# Zvuk9_R2.net
KiCad netlist of a schematic drawn in EAGLE
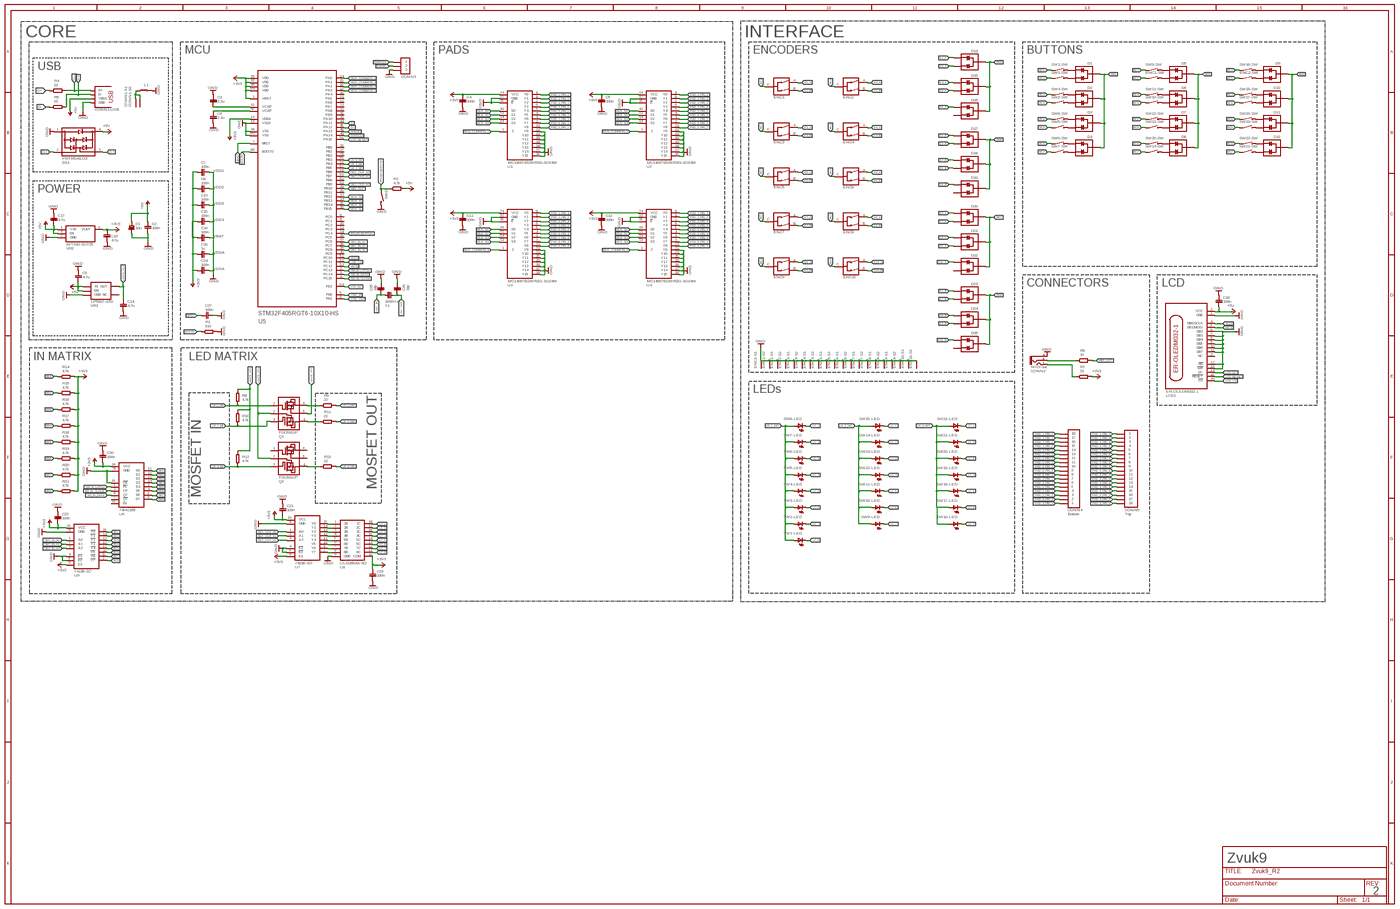
[diagram p0: schematic, sheet 1, overview]
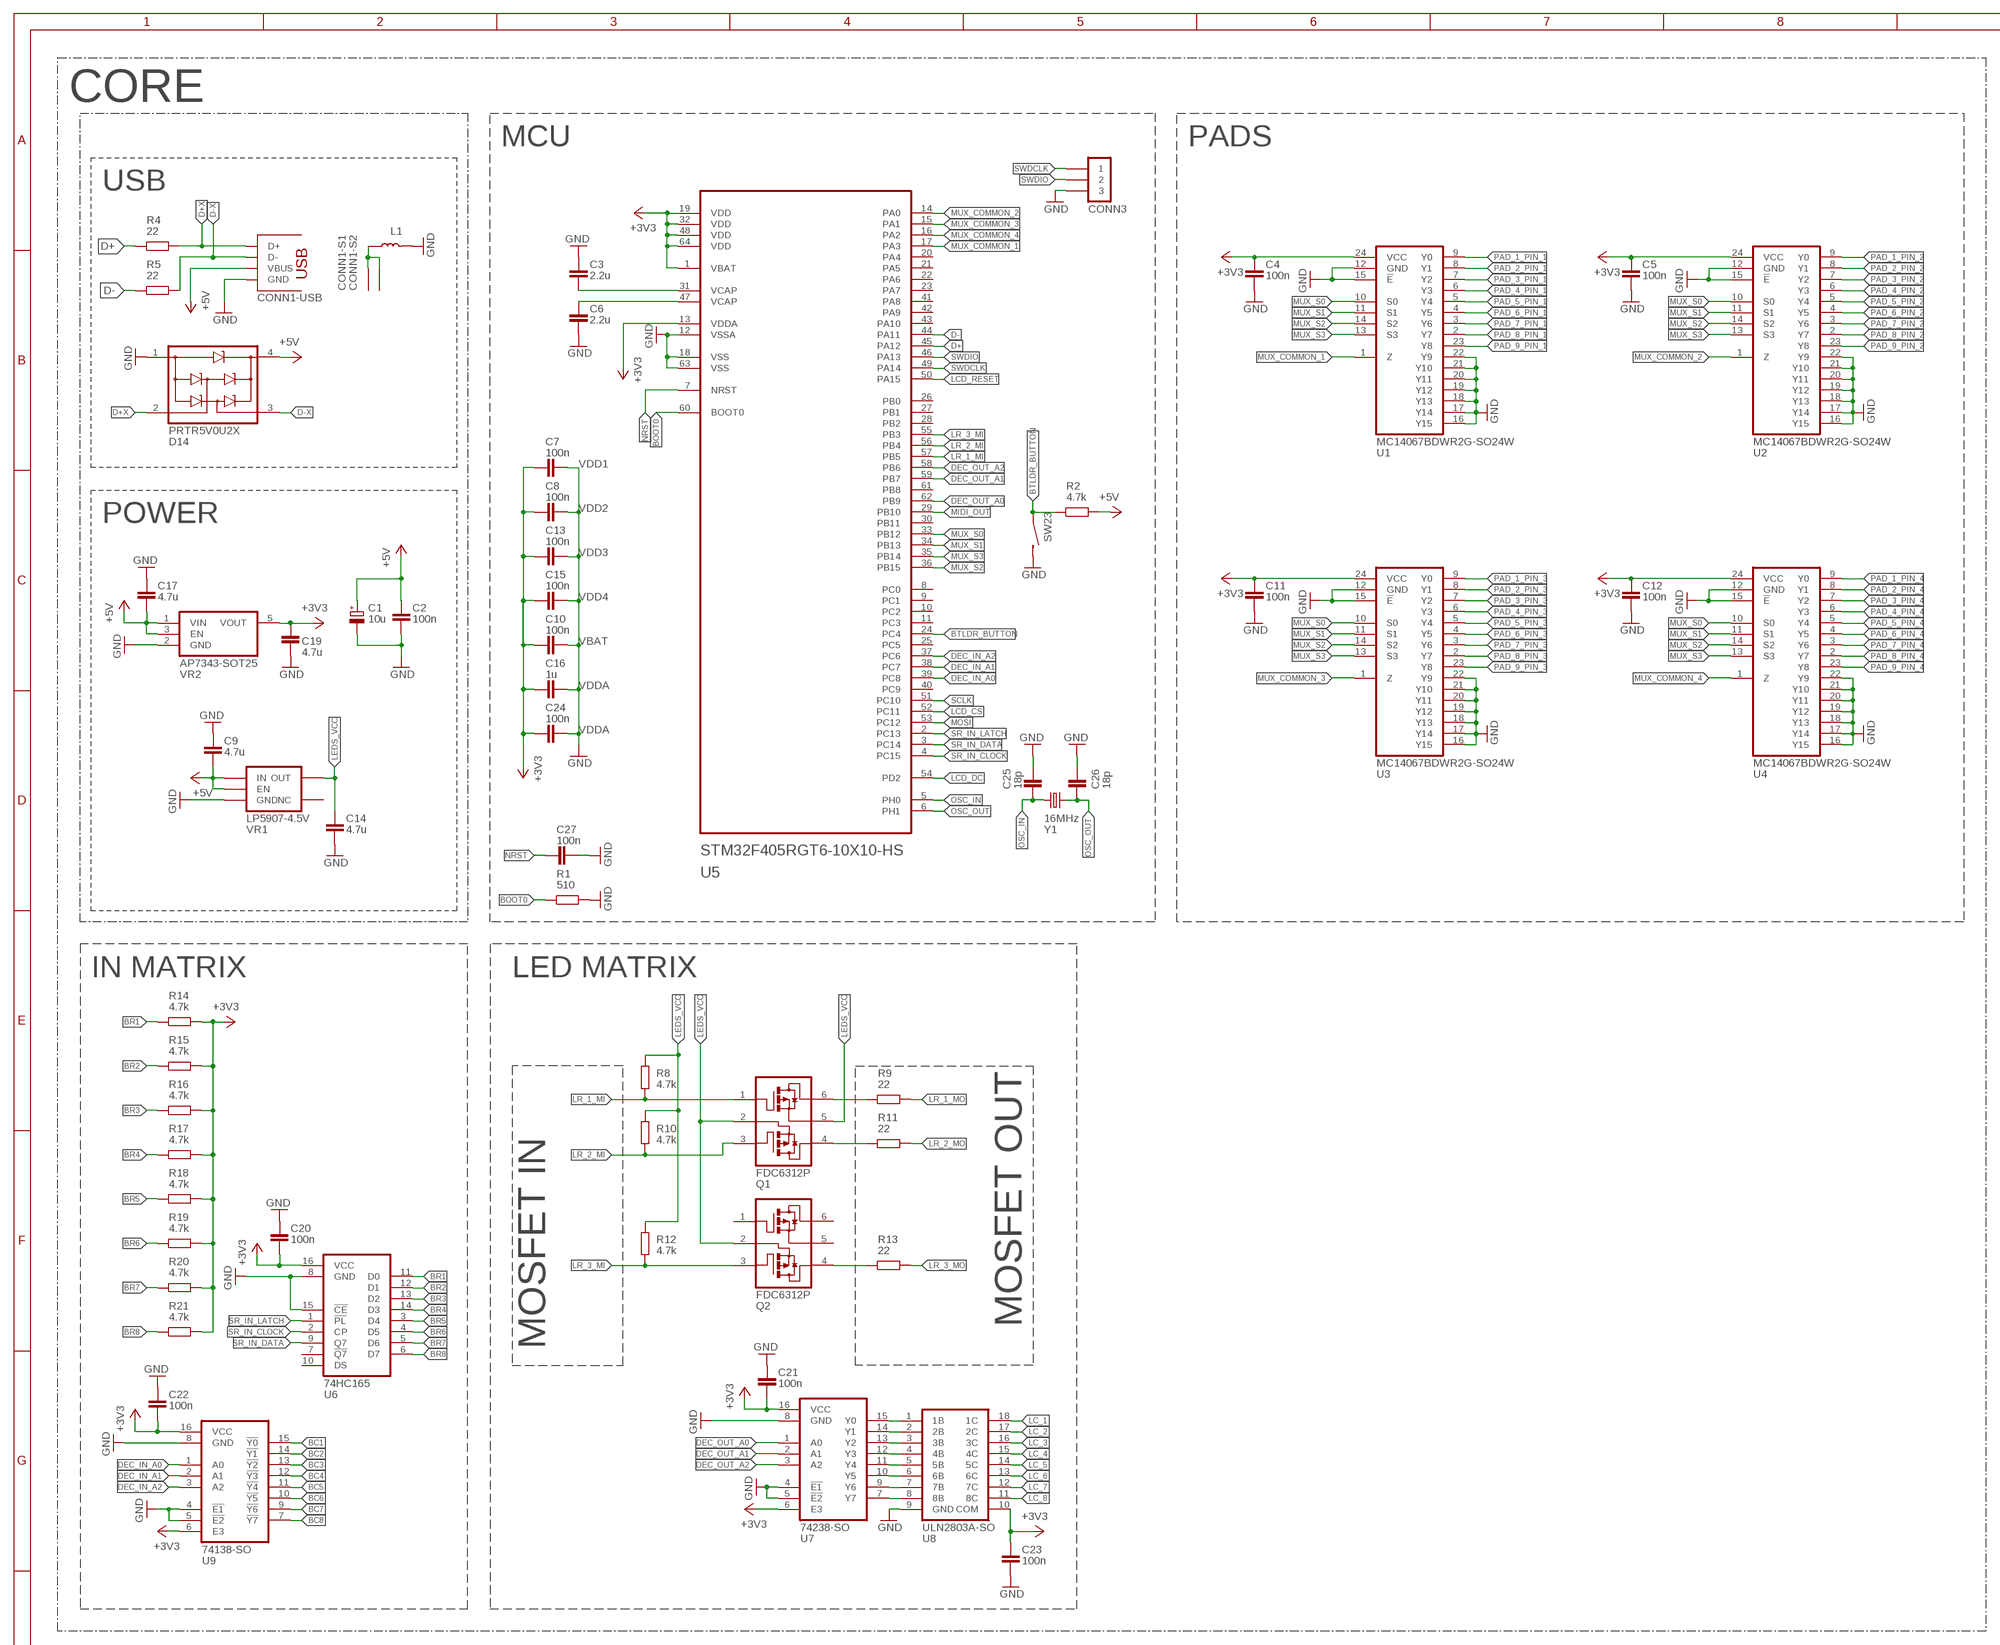
[diagram p1: schematic, sheet 1, part 1 of 4]
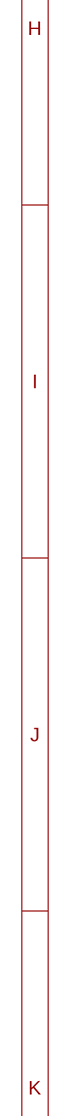
[diagram p2: schematic, sheet 1, part 2 of 4]
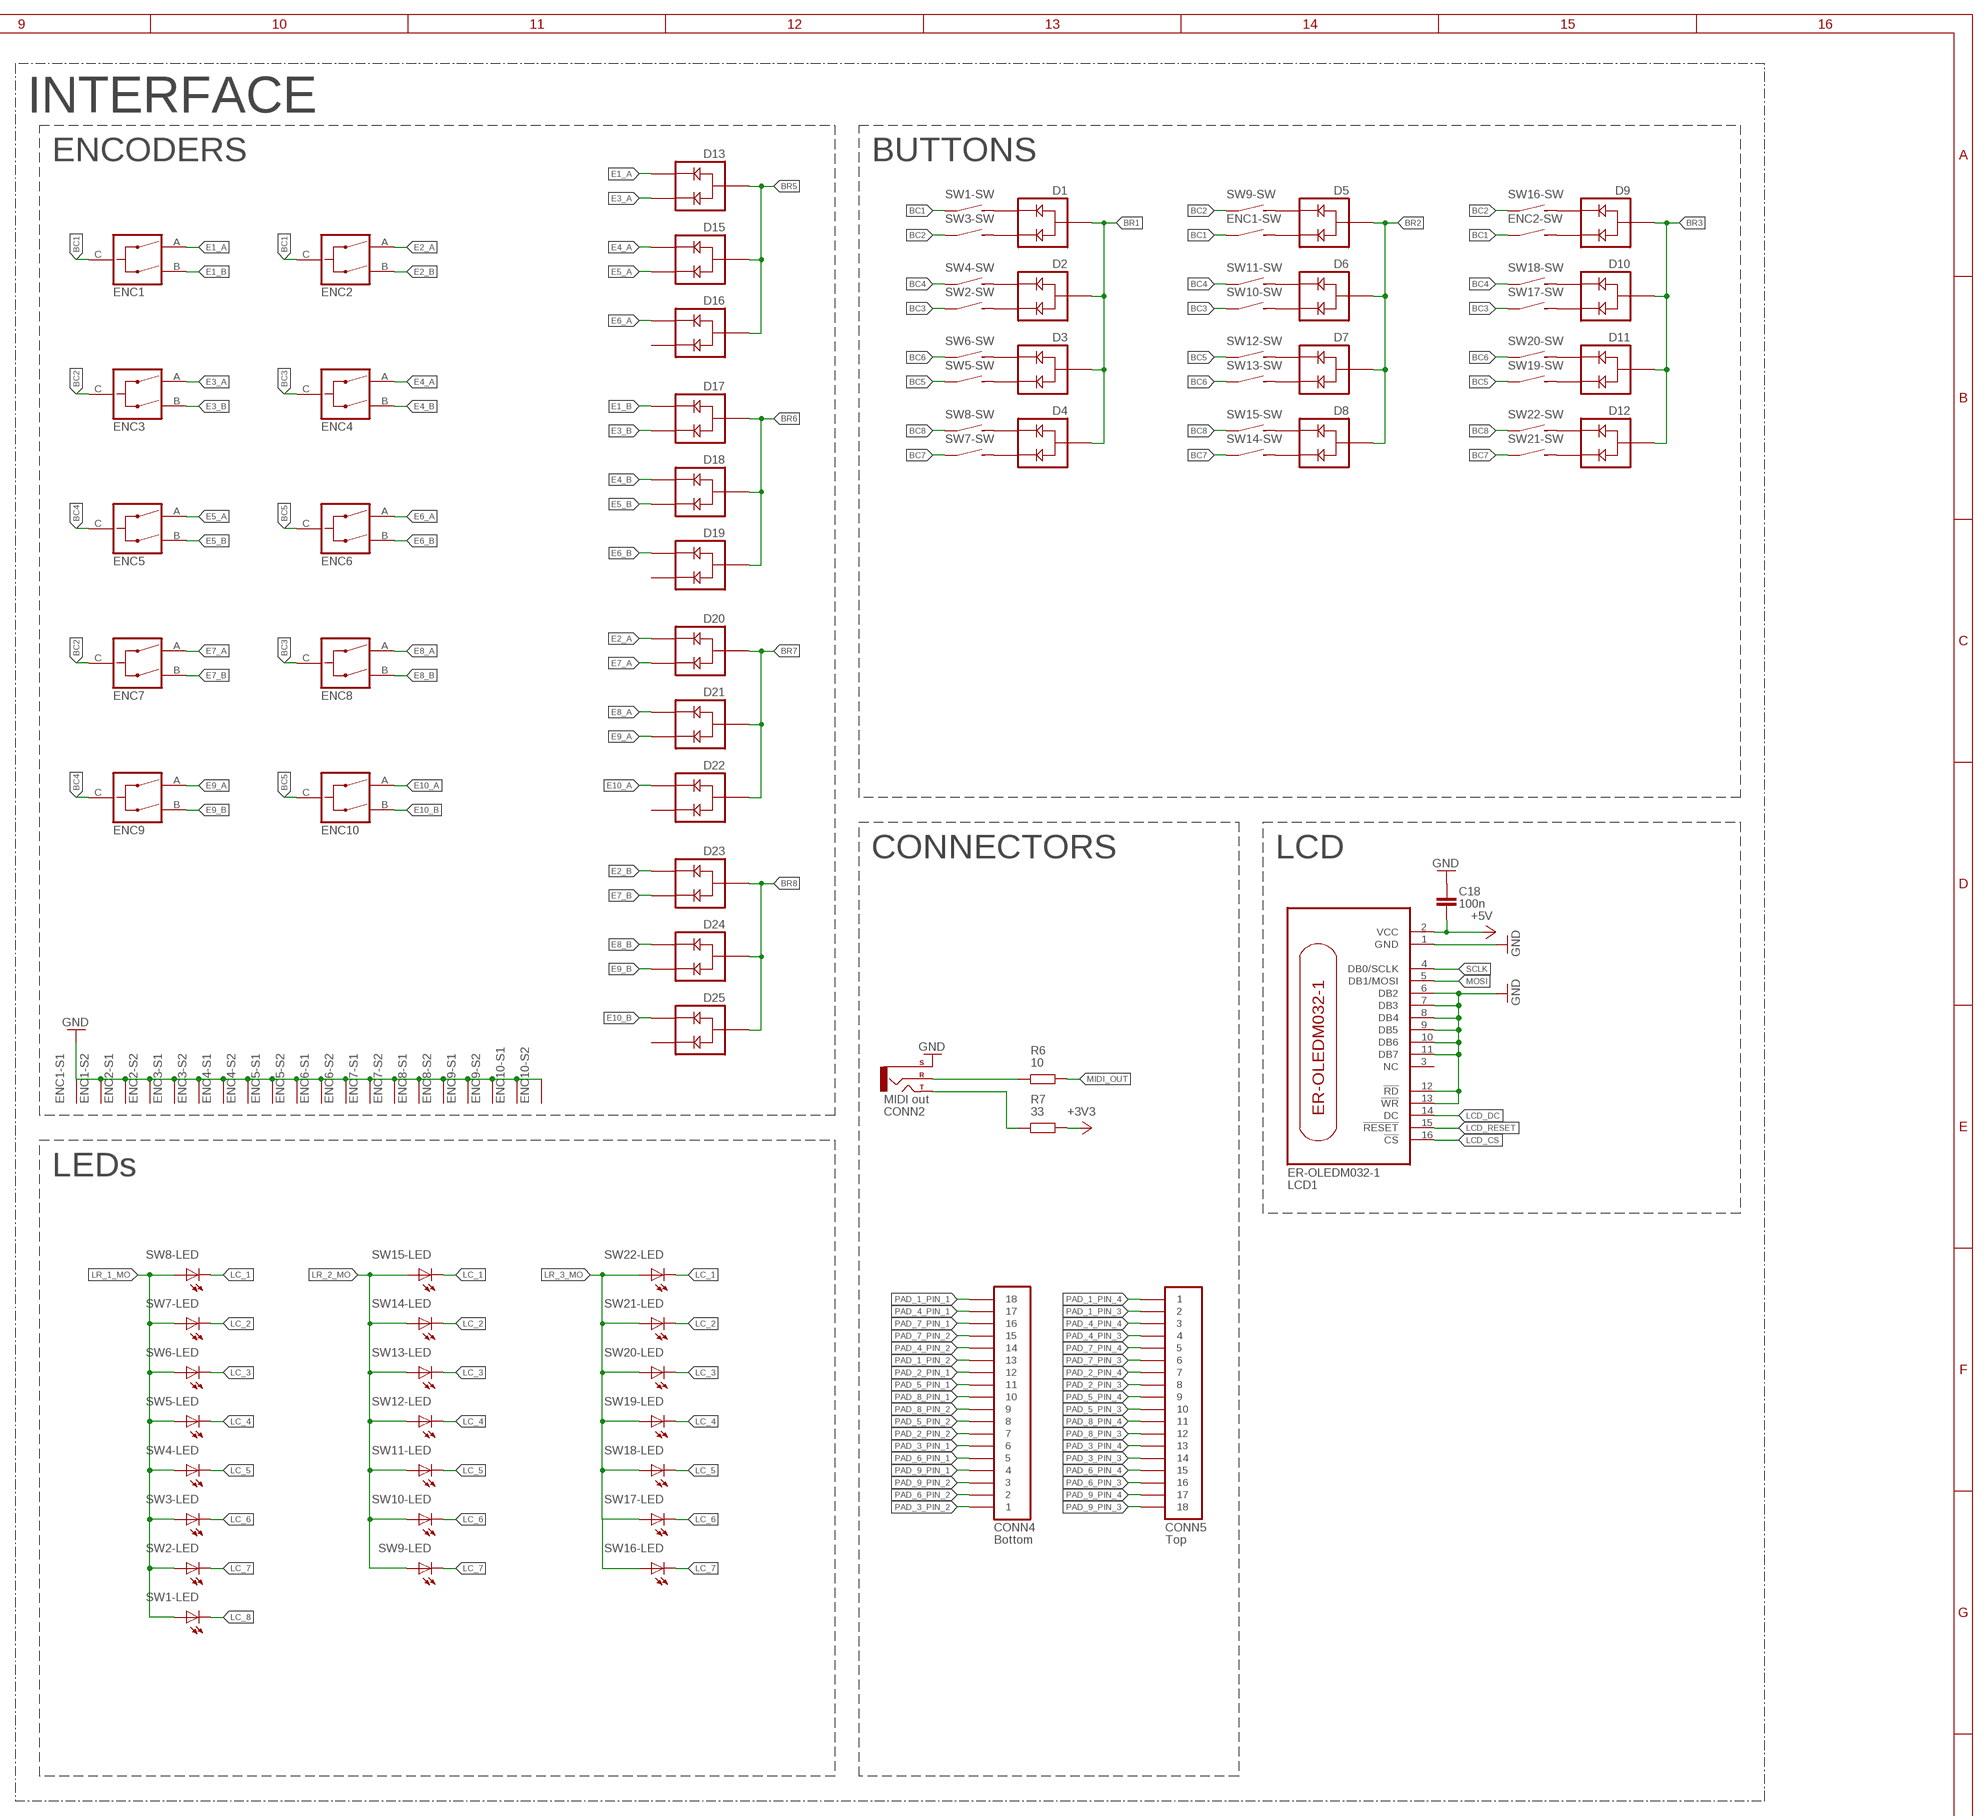
[diagram p3: schematic, sheet 1, part 3 of 4]
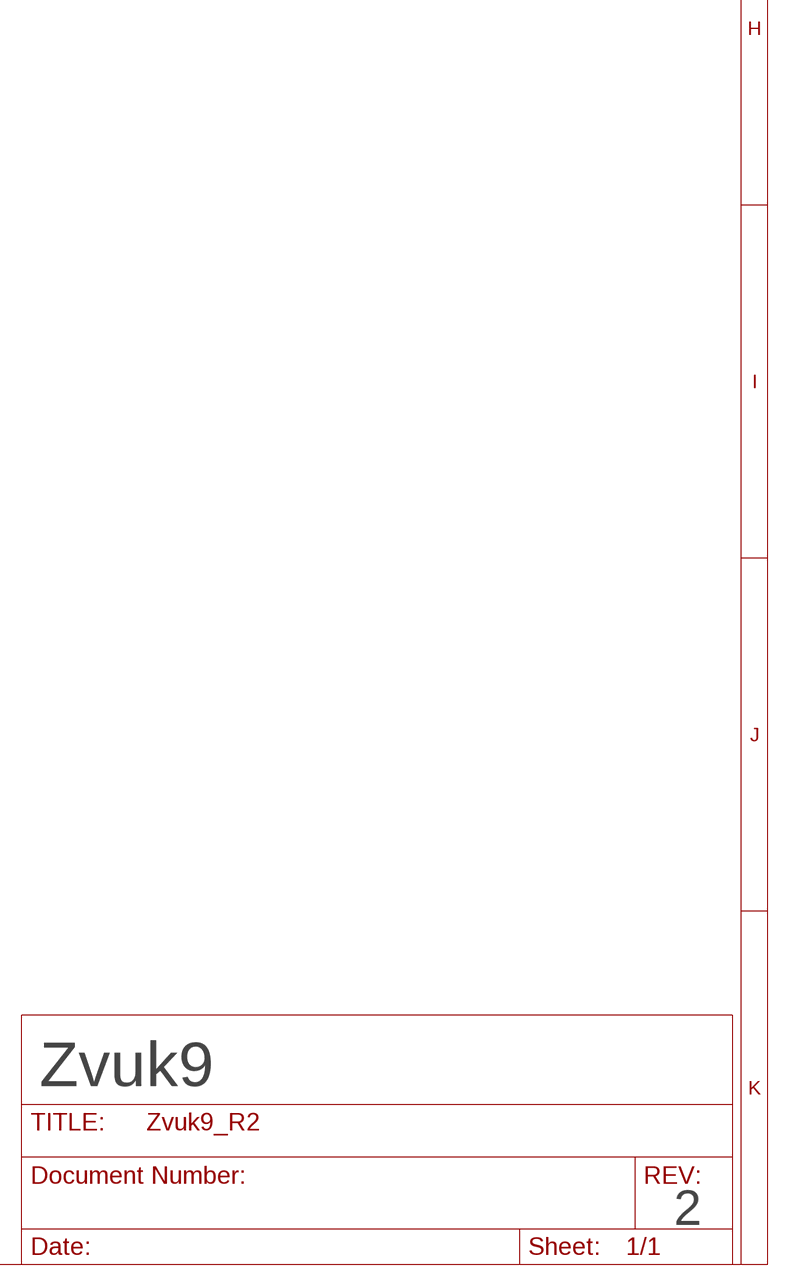
[diagram p4: schematic, sheet 1, part 4 of 4]

(export (version "E")
  (design (tool "Eeschema 10.0.6"))
  (components
    (comp (ref "C1")
      (value "10u")
      (footprint "eagle-import:C-TH-E-0502")
      (libsource (lib "eagle-import") (part "ELECTROLYTIC_CAPACITOR-C-TH-E-0502"))
    )
    (comp (ref "C2")
      (value "100n")
      (footprint "eagle-import:C0805")
      (libsource (lib "eagle-import") (part "CAPACITOR-0805"))
    )
    (comp (ref "C3")
      (value "2.2u")
      (footprint "eagle-import:C0805")
      (libsource (lib "eagle-import") (part "CAPACITOR-0805"))
    )
    (comp (ref "C4")
      (value "100n")
      (footprint "eagle-import:C0805")
      (libsource (lib "eagle-import") (part "CAPACITOR-0805"))
    )
    (comp (ref "C5")
      (value "100n")
      (footprint "eagle-import:C0805")
      (libsource (lib "eagle-import") (part "CAPACITOR-0805"))
    )
    (comp (ref "C6")
      (value "2.2u")
      (footprint "eagle-import:C0805")
      (libsource (lib "eagle-import") (part "CAPACITOR-0805"))
    )
    (comp (ref "C7")
      (value "100n")
      (footprint "eagle-import:C0805")
      (libsource (lib "eagle-import") (part "CAPACITOR-0805"))
    )
    (comp (ref "C8")
      (value "100n")
      (footprint "eagle-import:C0805")
      (libsource (lib "eagle-import") (part "CAPACITOR-0805"))
    )
    (comp (ref "C9")
      (value "4.7u")
      (footprint "eagle-import:C0805")
      (libsource (lib "eagle-import") (part "CAPACITOR-0805"))
    )
    (comp (ref "C10")
      (value "100n")
      (footprint "eagle-import:C0805")
      (libsource (lib "eagle-import") (part "CAPACITOR-0805"))
    )
    (comp (ref "C11")
      (value "100n")
      (footprint "eagle-import:C0805")
      (libsource (lib "eagle-import") (part "CAPACITOR-0805"))
    )
    (comp (ref "C12")
      (value "100n")
      (footprint "eagle-import:C0805")
      (libsource (lib "eagle-import") (part "CAPACITOR-0805"))
    )
    (comp (ref "C13")
      (value "100n")
      (footprint "eagle-import:C0805")
      (libsource (lib "eagle-import") (part "CAPACITOR-0805"))
    )
    (comp (ref "C14")
      (value "4.7u")
      (footprint "eagle-import:C0805")
      (libsource (lib "eagle-import") (part "CAPACITOR-0805"))
    )
    (comp (ref "C15")
      (value "100n")
      (footprint "eagle-import:C0805")
      (libsource (lib "eagle-import") (part "CAPACITOR-0805"))
    )
    (comp (ref "C16")
      (value "1u")
      (footprint "eagle-import:C0805")
      (libsource (lib "eagle-import") (part "CAPACITOR-0805"))
    )
    (comp (ref "C17")
      (value "4.7u")
      (footprint "eagle-import:C0805")
      (libsource (lib "eagle-import") (part "CAPACITOR-0805"))
    )
    (comp (ref "C18")
      (value "100n")
      (footprint "eagle-import:C0805")
      (libsource (lib "eagle-import") (part "CAPACITOR-0805"))
    )
    (comp (ref "C19")
      (value "4.7u")
      (footprint "eagle-import:C0805")
      (libsource (lib "eagle-import") (part "CAPACITOR-0805"))
    )
    (comp (ref "C20")
      (value "100n")
      (footprint "eagle-import:C0805")
      (libsource (lib "eagle-import") (part "CAPACITOR-0805"))
    )
    (comp (ref "C21")
      (value "100n")
      (footprint "eagle-import:C0805")
      (libsource (lib "eagle-import") (part "CAPACITOR-0805"))
    )
    (comp (ref "C22")
      (value "100n")
      (footprint "eagle-import:C0805")
      (libsource (lib "eagle-import") (part "CAPACITOR-0805"))
    )
    (comp (ref "C23")
      (value "100n")
      (footprint "eagle-import:C0805")
      (libsource (lib "eagle-import") (part "CAPACITOR-0805"))
    )
    (comp (ref "C24")
      (value "100n")
      (footprint "eagle-import:C0805")
      (libsource (lib "eagle-import") (part "CAPACITOR-0805"))
    )
    (comp (ref "C25")
      (value "18p")
      (footprint "eagle-import:C0805")
      (libsource (lib "eagle-import") (part "CAPACITOR-0805"))
    )
    (comp (ref "C26")
      (value "18p")
      (footprint "eagle-import:C0805")
      (libsource (lib "eagle-import") (part "CAPACITOR-0805"))
    )
    (comp (ref "C27")
      (value "100n")
      (footprint "eagle-import:C0805")
      (libsource (lib "eagle-import") (part "CAPACITOR-0805"))
    )
    (comp (ref "CONN1")
      (value "USB-B-H")
      (footprint "eagle-import:USB-B-PTH")
      (libsource (lib "eagle-import") (part "USB-B-H"))
    )
    (comp (ref "CONN2")
      (value "MIDI out")
      (footprint "eagle-import:SJ1-3523N")
      (libsource (lib "eagle-import") (part "3.5MM-AUDIO-3P-SJI-3523N"))
    )
    (comp (ref "CONN3")
      (value "PINHD-1X03-TH-2.54MM")
      (footprint "eagle-import:1X03-2.54-V")
      (libsource (lib "eagle-import") (part "PINHD-1X03-TH-2.54MM"))
    )
    (comp (ref "CONN4")
      (value "PINHD-1X18-FFC-SMD-1MM")
      (footprint "eagle-import:MOLEX-52271-1879")
      (libsource (lib "eagle-import") (part "PINHD-1X18-FFC-SMD-1MM"))
    )
    (comp (ref "CONN5")
      (value "PINHD-1X18-FFC-SMD-1MM")
      (footprint "eagle-import:MOLEX-52271-1879")
      (libsource (lib "eagle-import") (part "PINHD-1X18-FFC-SMD-1MM"))
    )
    (comp (ref "D1")
      (value "BAW56")
      (footprint "eagle-import:SOT23")
      (fields (field (name "MANUFACTURER") "Multicomp") (field (name "MPN") "BAW56-7-F"))
      (libsource (lib "eagle-import") (part "BAW56"))
    )
    (comp (ref "D2")
      (value "BAW56")
      (footprint "eagle-import:SOT23")
      (fields (field (name "MANUFACTURER") "Multicomp") (field (name "MPN") "BAW56-7-F"))
      (libsource (lib "eagle-import") (part "BAW56"))
    )
    (comp (ref "D3")
      (value "BAW56")
      (footprint "eagle-import:SOT23")
      (fields (field (name "MANUFACTURER") "Multicomp") (field (name "MPN") "BAW56-7-F"))
      (libsource (lib "eagle-import") (part "BAW56"))
    )
    (comp (ref "D4")
      (value "BAW56")
      (footprint "eagle-import:SOT23")
      (fields (field (name "MANUFACTURER") "Multicomp") (field (name "MPN") "BAW56-7-F"))
      (libsource (lib "eagle-import") (part "BAW56"))
    )
    (comp (ref "D5")
      (value "BAW56")
      (footprint "eagle-import:SOT23")
      (fields (field (name "MANUFACTURER") "Multicomp") (field (name "MPN") "BAW56-7-F"))
      (libsource (lib "eagle-import") (part "BAW56"))
    )
    (comp (ref "D6")
      (value "BAW56")
      (footprint "eagle-import:SOT23")
      (fields (field (name "MANUFACTURER") "Multicomp") (field (name "MPN") "BAW56-7-F"))
      (libsource (lib "eagle-import") (part "BAW56"))
    )
    (comp (ref "D7")
      (value "BAW56")
      (footprint "eagle-import:SOT23")
      (fields (field (name "MANUFACTURER") "Multicomp") (field (name "MPN") "BAW56-7-F"))
      (libsource (lib "eagle-import") (part "BAW56"))
    )
    (comp (ref "D8")
      (value "BAW56")
      (footprint "eagle-import:SOT23")
      (fields (field (name "MANUFACTURER") "Multicomp") (field (name "MPN") "BAW56-7-F"))
      (libsource (lib "eagle-import") (part "BAW56"))
    )
    (comp (ref "D9")
      (value "BAW56")
      (footprint "eagle-import:SOT23")
      (fields (field (name "MANUFACTURER") "Multicomp") (field (name "MPN") "BAW56-7-F"))
      (libsource (lib "eagle-import") (part "BAW56"))
    )
    (comp (ref "D10")
      (value "BAW56")
      (footprint "eagle-import:SOT23")
      (fields (field (name "MANUFACTURER") "Multicomp") (field (name "MPN") "BAW56-7-F"))
      (libsource (lib "eagle-import") (part "BAW56"))
    )
    (comp (ref "D11")
      (value "BAW56")
      (footprint "eagle-import:SOT23")
      (fields (field (name "MANUFACTURER") "Multicomp") (field (name "MPN") "BAW56-7-F"))
      (libsource (lib "eagle-import") (part "BAW56"))
    )
    (comp (ref "D12")
      (value "BAW56")
      (footprint "eagle-import:SOT23")
      (fields (field (name "MANUFACTURER") "Multicomp") (field (name "MPN") "BAW56-7-F"))
      (libsource (lib "eagle-import") (part "BAW56"))
    )
    (comp (ref "D13")
      (value "BAW56")
      (footprint "eagle-import:SOT23")
      (fields (field (name "MANUFACTURER") "Multicomp") (field (name "MPN") "BAW56-7-F"))
      (libsource (lib "eagle-import") (part "BAW56"))
    )
    (comp (ref "D14")
      (value "PRTR5V0U2X")
      (footprint "eagle-import:SOT143")
      (fields (field (name "MANUFACTURER") "Nexperia"))
      (libsource (lib "eagle-import") (part "PRTR5V0U2X"))
    )
    (comp (ref "D15")
      (value "BAW56")
      (footprint "eagle-import:SOT23")
      (fields (field (name "MANUFACTURER") "Multicomp") (field (name "MPN") "BAW56-7-F"))
      (libsource (lib "eagle-import") (part "BAW56"))
    )
    (comp (ref "D16")
      (value "BAW56")
      (footprint "eagle-import:SOT23")
      (fields (field (name "MANUFACTURER") "Multicomp") (field (name "MPN") "BAW56-7-F"))
      (libsource (lib "eagle-import") (part "BAW56"))
    )
    (comp (ref "D17")
      (value "BAW56")
      (footprint "eagle-import:SOT23")
      (fields (field (name "MANUFACTURER") "Multicomp") (field (name "MPN") "BAW56-7-F"))
      (libsource (lib "eagle-import") (part "BAW56"))
    )
    (comp (ref "D18")
      (value "BAW56")
      (footprint "eagle-import:SOT23")
      (fields (field (name "MANUFACTURER") "Multicomp") (field (name "MPN") "BAW56-7-F"))
      (libsource (lib "eagle-import") (part "BAW56"))
    )
    (comp (ref "D19")
      (value "BAW56")
      (footprint "eagle-import:SOT23")
      (fields (field (name "MANUFACTURER") "Multicomp") (field (name "MPN") "BAW56-7-F"))
      (libsource (lib "eagle-import") (part "BAW56"))
    )
    (comp (ref "D20")
      (value "BAW56")
      (footprint "eagle-import:SOT23")
      (fields (field (name "MANUFACTURER") "Multicomp") (field (name "MPN") "BAW56-7-F"))
      (libsource (lib "eagle-import") (part "BAW56"))
    )
    (comp (ref "D21")
      (value "BAW56")
      (footprint "eagle-import:SOT23")
      (fields (field (name "MANUFACTURER") "Multicomp") (field (name "MPN") "BAW56-7-F"))
      (libsource (lib "eagle-import") (part "BAW56"))
    )
    (comp (ref "D22")
      (value "BAW56")
      (footprint "eagle-import:SOT23")
      (fields (field (name "MANUFACTURER") "Multicomp") (field (name "MPN") "BAW56-7-F"))
      (libsource (lib "eagle-import") (part "BAW56"))
    )
    (comp (ref "D23")
      (value "BAW56")
      (footprint "eagle-import:SOT23")
      (fields (field (name "MANUFACTURER") "Multicomp") (field (name "MPN") "BAW56-7-F"))
      (libsource (lib "eagle-import") (part "BAW56"))
    )
    (comp (ref "D24")
      (value "BAW56")
      (footprint "eagle-import:SOT23")
      (fields (field (name "MANUFACTURER") "Multicomp") (field (name "MPN") "BAW56-7-F"))
      (libsource (lib "eagle-import") (part "BAW56"))
    )
    (comp (ref "D25")
      (value "BAW56")
      (footprint "eagle-import:SOT23")
      (fields (field (name "MANUFACTURER") "Multicomp") (field (name "MPN") "BAW56-7-F"))
      (libsource (lib "eagle-import") (part "BAW56"))
    )
    (comp (ref "ENC1")
      (value "ALPS-EC12D1524403")
      (footprint "eagle-import:ALPS_EC12-SW")
      (libsource (lib "eagle-import") (part "ALPS-EC12D1524403"))
    )
    (comp (ref "ENC2")
      (value "ALPS-EC12D1524403")
      (footprint "eagle-import:ALPS_EC12-SW")
      (libsource (lib "eagle-import") (part "ALPS-EC12D1524403"))
    )
    (comp (ref "ENC3")
      (value "ALPS-EC12E24404AX")
      (footprint "eagle-import:EC12E-1")
      (libsource (lib "eagle-import") (part "ALPS-EC12E24404AX"))
    )
    (comp (ref "ENC4")
      (value "ALPS-EC12E24404AX")
      (footprint "eagle-import:EC12E-1")
      (libsource (lib "eagle-import") (part "ALPS-EC12E24404AX"))
    )
    (comp (ref "ENC5")
      (value "ALPS-EC12E24404AX")
      (footprint "eagle-import:EC12E-1")
      (libsource (lib "eagle-import") (part "ALPS-EC12E24404AX"))
    )
    (comp (ref "ENC6")
      (value "ALPS-EC12E24404AX")
      (footprint "eagle-import:EC12E-1")
      (libsource (lib "eagle-import") (part "ALPS-EC12E24404AX"))
    )
    (comp (ref "ENC7")
      (value "ALPS-EC12E24404AX")
      (footprint "eagle-import:EC12E-1")
      (libsource (lib "eagle-import") (part "ALPS-EC12E24404AX"))
    )
    (comp (ref "ENC8")
      (value "ALPS-EC12E24404AX")
      (footprint "eagle-import:EC12E-1")
      (libsource (lib "eagle-import") (part "ALPS-EC12E24404AX"))
    )
    (comp (ref "ENC9")
      (value "ALPS-EC12E24404AX")
      (footprint "eagle-import:EC12E-1")
      (libsource (lib "eagle-import") (part "ALPS-EC12E24404AX"))
    )
    (comp (ref "ENC10")
      (value "ALPS-EC12E24404AX")
      (footprint "eagle-import:EC12E-1")
      (libsource (lib "eagle-import") (part "ALPS-EC12E24404AX"))
    )
    (comp (ref "L1")
      (value "FERRITE_BEAD-BLM21PG221SN1D")
      (footprint "eagle-import:L0805")
      (fields (field (name "MANUFACTURER") "Murata") (field (name "MPN") "BLM21PG221SN1D"))
      (libsource (lib "eagle-import") (part "FERRITE_BEAD-BLM21PG221SN1D"))
    )
    (comp (ref "LCD1")
      (value "ER-OLEDM032-1")
      (footprint "eagle-import:ER-OLEDM032-W")
      (libsource (lib "eagle-import") (part "ER-OLEDM032-1"))
    )
    (comp (ref "Q1")
      (value "FDC6312P")
      (footprint "eagle-import:SSOT6")
      (fields (field (name "MANUFACTURER") "ON Semiconductor"))
      (libsource (lib "eagle-import") (part "FDC6312P"))
    )
    (comp (ref "Q2")
      (value "FDC6312P")
      (footprint "eagle-import:SSOT6")
      (fields (field (name "MANUFACTURER") "ON Semiconductor"))
      (libsource (lib "eagle-import") (part "FDC6312P"))
    )
    (comp (ref "R1")
      (value "510")
      (footprint "eagle-import:R0805")
      (libsource (lib "eagle-import") (part "RESISTOR-0805"))
    )
    (comp (ref "R2")
      (value "4.7k")
      (footprint "eagle-import:R0805")
      (libsource (lib "eagle-import") (part "RESISTOR-0805"))
    )
    (comp (ref "R4")
      (value "22")
      (footprint "eagle-import:R0805")
      (libsource (lib "eagle-import") (part "RESISTOR-0805"))
    )
    (comp (ref "R5")
      (value "22")
      (footprint "eagle-import:R0805")
      (libsource (lib "eagle-import") (part "RESISTOR-0805"))
    )
    (comp (ref "R6")
      (value "10")
      (footprint "eagle-import:R0805")
      (libsource (lib "eagle-import") (part "RESISTOR-0805"))
    )
    (comp (ref "R7")
      (value "33")
      (footprint "eagle-import:R0805")
      (libsource (lib "eagle-import") (part "RESISTOR-0805"))
    )
    (comp (ref "R8")
      (value "4.7k")
      (footprint "eagle-import:R0805")
      (libsource (lib "eagle-import") (part "RESISTOR-0805"))
    )
    (comp (ref "R9")
      (value "22")
      (footprint "eagle-import:R0805")
      (libsource (lib "eagle-import") (part "RESISTOR-0805"))
    )
    (comp (ref "R10")
      (value "4.7k")
      (footprint "eagle-import:R0805")
      (libsource (lib "eagle-import") (part "RESISTOR-0805"))
    )
    (comp (ref "R11")
      (value "22")
      (footprint "eagle-import:R0805")
      (libsource (lib "eagle-import") (part "RESISTOR-0805"))
    )
    (comp (ref "R12")
      (value "4.7k")
      (footprint "eagle-import:R0805")
      (libsource (lib "eagle-import") (part "RESISTOR-0805"))
    )
    (comp (ref "R13")
      (value "22")
      (footprint "eagle-import:R0805")
      (libsource (lib "eagle-import") (part "RESISTOR-0805"))
    )
    (comp (ref "R14")
      (value "4.7k")
      (footprint "eagle-import:R0805")
      (libsource (lib "eagle-import") (part "RESISTOR-0805"))
    )
    (comp (ref "R15")
      (value "4.7k")
      (footprint "eagle-import:R0805")
      (libsource (lib "eagle-import") (part "RESISTOR-0805"))
    )
    (comp (ref "R16")
      (value "4.7k")
      (footprint "eagle-import:R0805")
      (libsource (lib "eagle-import") (part "RESISTOR-0805"))
    )
    (comp (ref "R17")
      (value "4.7k")
      (footprint "eagle-import:R0805")
      (libsource (lib "eagle-import") (part "RESISTOR-0805"))
    )
    (comp (ref "R18")
      (value "4.7k")
      (footprint "eagle-import:R0805")
      (libsource (lib "eagle-import") (part "RESISTOR-0805"))
    )
    (comp (ref "R19")
      (value "4.7k")
      (footprint "eagle-import:R0805")
      (libsource (lib "eagle-import") (part "RESISTOR-0805"))
    )
    (comp (ref "R20")
      (value "4.7k")
      (footprint "eagle-import:R0805")
      (libsource (lib "eagle-import") (part "RESISTOR-0805"))
    )
    (comp (ref "R21")
      (value "4.7k")
      (footprint "eagle-import:R0805")
      (libsource (lib "eagle-import") (part "RESISTOR-0805"))
    )
    (comp (ref "SW1")
      (value "OMRON-B3W-9")
      (footprint "eagle-import:OMRON-B3W-9")
      (libsource (lib "eagle-import") (part "OMRON-B3W-9"))
    )
    (comp (ref "SW2")
      (value "OMRON-B3W-9")
      (footprint "eagle-import:OMRON-B3W-9")
      (libsource (lib "eagle-import") (part "OMRON-B3W-9"))
    )
    (comp (ref "SW3")
      (value "OMRON-B3W-9")
      (footprint "eagle-import:OMRON-B3W-9")
      (libsource (lib "eagle-import") (part "OMRON-B3W-9"))
    )
    (comp (ref "SW4")
      (value "OMRON-B3W-9")
      (footprint "eagle-import:OMRON-B3W-9")
      (libsource (lib "eagle-import") (part "OMRON-B3W-9"))
    )
    (comp (ref "SW5")
      (value "OMRON-B3W-9")
      (footprint "eagle-import:OMRON-B3W-9")
      (libsource (lib "eagle-import") (part "OMRON-B3W-9"))
    )
    (comp (ref "SW6")
      (value "OMRON-B3W-9")
      (footprint "eagle-import:OMRON-B3W-9")
      (libsource (lib "eagle-import") (part "OMRON-B3W-9"))
    )
    (comp (ref "SW7")
      (value "OMRON-B3W-9")
      (footprint "eagle-import:OMRON-B3W-9")
      (libsource (lib "eagle-import") (part "OMRON-B3W-9"))
    )
    (comp (ref "SW8")
      (value "OMRON-B3W-9")
      (footprint "eagle-import:OMRON-B3W-9")
      (libsource (lib "eagle-import") (part "OMRON-B3W-9"))
    )
    (comp (ref "SW9")
      (value "OMRON-B3W-9")
      (footprint "eagle-import:OMRON-B3W-9")
      (libsource (lib "eagle-import") (part "OMRON-B3W-9"))
    )
    (comp (ref "SW10")
      (value "OMRON-B3W-9")
      (footprint "eagle-import:OMRON-B3W-9")
      (libsource (lib "eagle-import") (part "OMRON-B3W-9"))
    )
    (comp (ref "SW11")
      (value "OMRON-B3W-9")
      (footprint "eagle-import:OMRON-B3W-9")
      (libsource (lib "eagle-import") (part "OMRON-B3W-9"))
    )
    (comp (ref "SW12")
      (value "OMRON-B3W-9")
      (footprint "eagle-import:OMRON-B3W-9")
      (libsource (lib "eagle-import") (part "OMRON-B3W-9"))
    )
    (comp (ref "SW13")
      (value "OMRON-B3W-9")
      (footprint "eagle-import:OMRON-B3W-9")
      (libsource (lib "eagle-import") (part "OMRON-B3W-9"))
    )
    (comp (ref "SW14")
      (value "OMRON-B3W-9")
      (footprint "eagle-import:OMRON-B3W-9")
      (libsource (lib "eagle-import") (part "OMRON-B3W-9"))
    )
    (comp (ref "SW15")
      (value "OMRON-B3W-9")
      (footprint "eagle-import:OMRON-B3W-9")
      (libsource (lib "eagle-import") (part "OMRON-B3W-9"))
    )
    (comp (ref "SW16")
      (value "OMRON-B3W-9")
      (footprint "eagle-import:OMRON-B3W-9")
      (libsource (lib "eagle-import") (part "OMRON-B3W-9"))
    )
    (comp (ref "SW17")
      (value "OMRON-B3W-9")
      (footprint "eagle-import:OMRON-B3W-9")
      (libsource (lib "eagle-import") (part "OMRON-B3W-9"))
    )
    (comp (ref "SW18")
      (value "OMRON-B3W-9")
      (footprint "eagle-import:OMRON-B3W-9")
      (libsource (lib "eagle-import") (part "OMRON-B3W-9"))
    )
    (comp (ref "SW19")
      (value "OMRON-B3W-9")
      (footprint "eagle-import:OMRON-B3W-9")
      (libsource (lib "eagle-import") (part "OMRON-B3W-9"))
    )
    (comp (ref "SW20")
      (value "OMRON-B3W-9")
      (footprint "eagle-import:OMRON-B3W-9")
      (libsource (lib "eagle-import") (part "OMRON-B3W-9"))
    )
    (comp (ref "SW21")
      (value "OMRON-B3W-9")
      (footprint "eagle-import:OMRON-B3W-9")
      (libsource (lib "eagle-import") (part "OMRON-B3W-9"))
    )
    (comp (ref "SW22")
      (value "OMRON-B3W-9")
      (footprint "eagle-import:OMRON-B3W-9")
      (libsource (lib "eagle-import") (part "OMRON-B3W-9"))
    )
    (comp (ref "SW23")
      (value "SWITCH-B3F")
      (footprint "eagle-import:B3F-312X")
      (libsource (lib "eagle-import") (part "SWITCH-B3F"))
    )
    (comp (ref "U1")
      (value "MC14067BDWR2G-SO24W")
      (footprint "eagle-import:SO24-W")
      (fields (field (name "MANUFACTURER") "ON Semiconductor") (field (name "MPN") "MC14067BDWR2G"))
      (libsource (lib "eagle-import") (part "MC14067BDWR2G-SO24W"))
    )
    (comp (ref "U2")
      (value "MC14067BDWR2G-SO24W")
      (footprint "eagle-import:SO24-W")
      (fields (field (name "MANUFACTURER") "ON Semiconductor") (field (name "MPN") "MC14067BDWR2G"))
      (libsource (lib "eagle-import") (part "MC14067BDWR2G-SO24W"))
    )
    (comp (ref "U3")
      (value "MC14067BDWR2G-SO24W")
      (footprint "eagle-import:SO24-W")
      (fields (field (name "MANUFACTURER") "ON Semiconductor") (field (name "MPN") "MC14067BDWR2G"))
      (libsource (lib "eagle-import") (part "MC14067BDWR2G-SO24W"))
    )
    (comp (ref "U4")
      (value "MC14067BDWR2G-SO24W")
      (footprint "eagle-import:SO24-W")
      (fields (field (name "MANUFACTURER") "ON Semiconductor") (field (name "MPN") "MC14067BDWR2G"))
      (libsource (lib "eagle-import") (part "MC14067BDWR2G-SO24W"))
    )
    (comp (ref "U5")
      (value "STM32F405RGT6-10X10-HS")
      (footprint "eagle-import:TQFP-64-10X10-HS")
      (libsource (lib "eagle-import") (part "STM32F405RGT6-10X10-HS"))
    )
    (comp (ref "U6")
      (value "74HC165")
      (footprint "eagle-import:SO16")
      (fields (field (name "MANUFACTURER") "Nexperia") (field (name "MPN") "74HC165D"))
      (libsource (lib "eagle-import") (part "74165HC"))
    )
    (comp (ref "U7")
      (value "74238-SO")
      (footprint "eagle-import:SO16")
      (fields (field (name "MANUFACTURER") "Nexperia") (field (name "MPN") "74HC238D"))
      (libsource (lib "eagle-import") (part "74238-SOHC"))
    )
    (comp (ref "U8")
      (value "ULN2803A-SO")
      (footprint "eagle-import:SO18")
      (fields (field (name "MANUFACTURER") "Texas Instruments") (field (name "MPN") "ULN2803ADWR"))
      (libsource (lib "eagle-import") (part "ULN2803A-SO"))
    )
    (comp (ref "U9")
      (value "74138-SO")
      (footprint "eagle-import:SO16")
      (fields (field (name "MANUFACTURER") "Nexperia") (field (name "MPN") "74HC138D"))
      (libsource (lib "eagle-import") (part "74138-SOHC"))
    )
    (comp (ref "VR1")
      (value "LP5907-4.5V")
      (footprint "eagle-import:SOT23-5")
      (fields (field (name "MANUFACTURER") "Texas Instruments") (field (name "MPN") "LP5907MFX-4.5/NOPB"))
      (libsource (lib "eagle-import") (part "LP5907-4.5V"))
    )
    (comp (ref "VR2")
      (value "AP7343-SOT25")
      (footprint "eagle-import:SOT25")
      (fields (field (name "MANUFACTURER") "Diodes Incorporated") (field (name "MPN") "AP7343"))
      (libsource (lib "eagle-import") (part "AP7343-SOT25"))
    )
    (comp (ref "Y1")
      (value "16MHz")
      (footprint "eagle-import:HC49US")
      (fields (field (name "MANUFACTURER") "TXC") (field (name "MPN") "9B-16.000MEEJ-B"))
      (libsource (lib "eagle-import") (part "CRYSTAL-HC49"))
    )
  )
  (nets
    (net (code "1") (name "+3V3") (class "Default")
      (node (ref "C10") (pin "1") (pinfunction "1_1") (pintype "passive"))
      (node (ref "C11") (pin "1") (pinfunction "1_1") (pintype "passive"))
      (node (ref "C12") (pin "1") (pinfunction "1_1") (pintype "passive"))
      (node (ref "C13") (pin "1") (pinfunction "1_1") (pintype "passive"))
      (node (ref "C15") (pin "1") (pinfunction "1_1") (pintype "passive"))
      (node (ref "C16") (pin "1") (pinfunction "1_1") (pintype "passive"))
      (node (ref "C19") (pin "1") (pinfunction "1_1") (pintype "passive"))
      (node (ref "C20") (pin "2") (pinfunction "2_2") (pintype "passive"))
      (node (ref "C21") (pin "2") (pinfunction "2_2") (pintype "passive"))
      (node (ref "C22") (pin "2") (pinfunction "2_2") (pintype "passive"))
      (node (ref "C23") (pin "1") (pinfunction "1_1") (pintype "passive"))
      (node (ref "C24") (pin "1") (pinfunction "1_1") (pintype "passive"))
      (node (ref "C4") (pin "1") (pinfunction "1_1") (pintype "passive"))
      (node (ref "C5") (pin "1") (pinfunction "1_1") (pintype "passive"))
      (node (ref "C7") (pin "1") (pinfunction "1_1") (pintype "passive"))
      (node (ref "C8") (pin "1") (pinfunction "1_1") (pintype "passive"))
      (node (ref "R14") (pin "2") (pinfunction "2_2") (pintype "passive"))
      (node (ref "R15") (pin "2") (pinfunction "2_2") (pintype "passive"))
      (node (ref "R16") (pin "2") (pinfunction "2_2") (pintype "passive"))
      (node (ref "R17") (pin "2") (pinfunction "2_2") (pintype "passive"))
      (node (ref "R18") (pin "2") (pinfunction "2_2") (pintype "passive"))
      (node (ref "R19") (pin "2") (pinfunction "2_2") (pintype "passive"))
      (node (ref "R20") (pin "2") (pinfunction "2_2") (pintype "passive"))
      (node (ref "R21") (pin "2") (pinfunction "2_2") (pintype "passive"))
      (node (ref "R7") (pin "2") (pinfunction "2_2") (pintype "passive"))
      (node (ref "U1") (pin "24") (pinfunction "VCC_24") (pintype "passive"))
      (node (ref "U2") (pin "24") (pinfunction "VCC_24") (pintype "passive"))
      (node (ref "U3") (pin "24") (pinfunction "VCC_24") (pintype "passive"))
      (node (ref "U4") (pin "24") (pinfunction "VCC_24") (pintype "passive"))
      (node (ref "U5") (pin "1") (pinfunction "VBAT_1") (pintype "bidirectional"))
      (node (ref "U5") (pin "13") (pinfunction "VDDA_13") (pintype "bidirectional"))
      (node (ref "U5") (pin "19") (pinfunction "VDD_19") (pintype "bidirectional"))
      (node (ref "U5") (pin "32") (pinfunction "VDD_32") (pintype "bidirectional"))
      (node (ref "U5") (pin "48") (pinfunction "VDD_48") (pintype "bidirectional"))
      (node (ref "U5") (pin "64") (pinfunction "VDD_64") (pintype "bidirectional"))
      (node (ref "U6") (pin "16") (pinfunction "VCC_16") (pintype "power_in"))
      (node (ref "U7") (pin "16") (pinfunction "VCC_16") (pintype "power_in"))
      (node (ref "U7") (pin "6") (pinfunction "E3_6") (pintype "input"))
      (node (ref "U8") (pin "10") (pinfunction "COM_10") (pintype "passive"))
      (node (ref "U9") (pin "16") (pinfunction "VCC_16") (pintype "power_in"))
      (node (ref "U9") (pin "6") (pinfunction "E3_6") (pintype "input"))
      (node (ref "VR2") (pin "5") (pinfunction "VOUT_5") (pintype "passive"))
    )
    (net (code "2") (name "+5V") (class "Default")
      (node (ref "C1") (pin "+") (pinfunction "+_+") (pintype "passive"))
      (node (ref "C17") (pin "2") (pinfunction "2_2") (pintype "passive"))
      (node (ref "C18") (pin "2") (pinfunction "2_2") (pintype "passive"))
      (node (ref "C2") (pin "1") (pinfunction "1_1") (pintype "passive"))
      (node (ref "C9") (pin "2") (pinfunction "2_2") (pintype "passive"))
      (node (ref "CONN1") (pin "VBUS") (pinfunction "VBUS_VBUS") (pintype "bidirectional"))
      (node (ref "D14") (pin "4") (pinfunction "VCC_4") (pintype "passive"))
      (node (ref "LCD1") (pin "2") (pinfunction "VCC_2") (pintype "power_in"))
      (node (ref "R2") (pin "2") (pinfunction "2_2") (pintype "passive"))
      (node (ref "VR1") (pin "1") (pinfunction "IN_1") (pintype "power_in"))
      (node (ref "VR1") (pin "3") (pinfunction "EN_3") (pintype "input"))
      (node (ref "VR2") (pin "1") (pinfunction "VIN_1") (pintype "passive"))
      (node (ref "VR2") (pin "3") (pinfunction "EN_3") (pintype "passive"))
    )
    (net (code "3") (name "BC1") (class "Default")
      (node (ref "ENC1") (pin "C") (pinfunction "C_C") (pintype "input"))
      (node (ref "ENC1") (pin "D") (pinfunction "1_D") (pintype "passive"))
      (node (ref "ENC2") (pin "C") (pinfunction "C_C") (pintype "input"))
      (node (ref "ENC2") (pin "D") (pinfunction "1_D") (pintype "passive"))
      (node (ref "SW1") (pin "1") (pinfunction "1_1") (pintype "passive"))
      (node (ref "U9") (pin "15") (pinfunction "~{Y0}_15") (pintype "output"))
    )
    (net (code "4") (name "BC2") (class "Default")
      (node (ref "ENC3") (pin "C") (pinfunction "C_C") (pintype "input"))
      (node (ref "ENC7") (pin "C") (pinfunction "C_C") (pintype "input"))
      (node (ref "SW16") (pin "1") (pinfunction "1_1") (pintype "passive"))
      (node (ref "SW3") (pin "1") (pinfunction "1_1") (pintype "passive"))
      (node (ref "SW9") (pin "1") (pinfunction "1_1") (pintype "passive"))
      (node (ref "U9") (pin "14") (pinfunction "~{Y1}_14") (pintype "output"))
    )
    (net (code "5") (name "BC3") (class "Default")
      (node (ref "ENC4") (pin "C") (pinfunction "C_C") (pintype "input"))
      (node (ref "ENC8") (pin "C") (pinfunction "C_C") (pintype "input"))
      (node (ref "SW10") (pin "1") (pinfunction "1_1") (pintype "passive"))
      (node (ref "SW17") (pin "1") (pinfunction "1_1") (pintype "passive"))
      (node (ref "SW2") (pin "1") (pinfunction "1_1") (pintype "passive"))
      (node (ref "U9") (pin "13") (pinfunction "~{Y2}_13") (pintype "output"))
    )
    (net (code "6") (name "BC4") (class "Default")
      (node (ref "ENC5") (pin "C") (pinfunction "C_C") (pintype "input"))
      (node (ref "ENC9") (pin "C") (pinfunction "C_C") (pintype "input"))
      (node (ref "SW11") (pin "1") (pinfunction "1_1") (pintype "passive"))
      (node (ref "SW18") (pin "1") (pinfunction "1_1") (pintype "passive"))
      (node (ref "SW4") (pin "1") (pinfunction "1_1") (pintype "passive"))
      (node (ref "U9") (pin "12") (pinfunction "~{Y3}_12") (pintype "output"))
    )
    (net (code "7") (name "BC5") (class "Default")
      (node (ref "ENC10") (pin "C") (pinfunction "C_C") (pintype "input"))
      (node (ref "ENC6") (pin "C") (pinfunction "C_C") (pintype "input"))
      (node (ref "SW12") (pin "1") (pinfunction "1_1") (pintype "passive"))
      (node (ref "SW19") (pin "1") (pinfunction "1_1") (pintype "passive"))
      (node (ref "SW5") (pin "1") (pinfunction "1_1") (pintype "passive"))
      (node (ref "U9") (pin "11") (pinfunction "~{Y4}_11") (pintype "output"))
    )
    (net (code "8") (name "BC6") (class "Default")
      (node (ref "SW13") (pin "1") (pinfunction "1_1") (pintype "passive"))
      (node (ref "SW20") (pin "1") (pinfunction "1_1") (pintype "passive"))
      (node (ref "SW6") (pin "1") (pinfunction "1_1") (pintype "passive"))
      (node (ref "U9") (pin "10") (pinfunction "~{Y5}_10") (pintype "output"))
    )
    (net (code "9") (name "BC7") (class "Default")
      (node (ref "SW14") (pin "1") (pinfunction "1_1") (pintype "passive"))
      (node (ref "SW21") (pin "1") (pinfunction "1_1") (pintype "passive"))
      (node (ref "SW7") (pin "1") (pinfunction "1_1") (pintype "passive"))
      (node (ref "U9") (pin "9") (pinfunction "~{Y6}_9") (pintype "output"))
    )
    (net (code "10") (name "BC8") (class "Default")
      (node (ref "SW15") (pin "1") (pinfunction "1_1") (pintype "passive"))
      (node (ref "SW22") (pin "1") (pinfunction "1_1") (pintype "passive"))
      (node (ref "SW8") (pin "1") (pinfunction "1_1") (pintype "passive"))
      (node (ref "U9") (pin "7") (pinfunction "~{Y7}_7") (pintype "output"))
    )
    (net (code "11") (name "BOOT0") (class "Default")
      (node (ref "R1") (pin "1") (pinfunction "1_1") (pintype "passive"))
      (node (ref "U5") (pin "60") (pinfunction "BOOT0_60") (pintype "bidirectional"))
    )
    (net (code "12") (name "BR1") (class "Default")
      (node (ref "D1") (pin "3") (pinfunction "3_3") (pintype "passive"))
      (node (ref "D2") (pin "3") (pinfunction "3_3") (pintype "passive"))
      (node (ref "D3") (pin "3") (pinfunction "3_3") (pintype "passive"))
      (node (ref "D4") (pin "3") (pinfunction "3_3") (pintype "passive"))
      (node (ref "R14") (pin "1") (pinfunction "1_1") (pintype "passive"))
      (node (ref "U6") (pin "11") (pinfunction "D0_11") (pintype "input"))
    )
    (net (code "13") (name "BR2") (class "Default")
      (node (ref "D5") (pin "3") (pinfunction "3_3") (pintype "passive"))
      (node (ref "D6") (pin "3") (pinfunction "3_3") (pintype "passive"))
      (node (ref "D7") (pin "3") (pinfunction "3_3") (pintype "passive"))
      (node (ref "D8") (pin "3") (pinfunction "3_3") (pintype "passive"))
      (node (ref "R15") (pin "1") (pinfunction "1_1") (pintype "passive"))
      (node (ref "U6") (pin "12") (pinfunction "D1_12") (pintype "input"))
    )
    (net (code "14") (name "BR3") (class "Default")
      (node (ref "D10") (pin "3") (pinfunction "3_3") (pintype "passive"))
      (node (ref "D11") (pin "3") (pinfunction "3_3") (pintype "passive"))
      (node (ref "D12") (pin "3") (pinfunction "3_3") (pintype "passive"))
      (node (ref "D9") (pin "3") (pinfunction "3_3") (pintype "passive"))
      (node (ref "R16") (pin "1") (pinfunction "1_1") (pintype "passive"))
      (node (ref "U6") (pin "13") (pinfunction "D2_13") (pintype "input"))
    )
    (net (code "15") (name "BR4") (class "Default")
      (node (ref "R17") (pin "1") (pinfunction "1_1") (pintype "passive"))
      (node (ref "U6") (pin "14") (pinfunction "D3_14") (pintype "input"))
    )
    (net (code "16") (name "BR5") (class "Default")
      (node (ref "D13") (pin "3") (pinfunction "3_3") (pintype "passive"))
      (node (ref "D15") (pin "3") (pinfunction "3_3") (pintype "passive"))
      (node (ref "D16") (pin "3") (pinfunction "3_3") (pintype "passive"))
      (node (ref "R18") (pin "1") (pinfunction "1_1") (pintype "passive"))
      (node (ref "U6") (pin "3") (pinfunction "D4_3") (pintype "input"))
    )
    (net (code "17") (name "BR6") (class "Default")
      (node (ref "D17") (pin "3") (pinfunction "3_3") (pintype "passive"))
      (node (ref "D18") (pin "3") (pinfunction "3_3") (pintype "passive"))
      (node (ref "D19") (pin "3") (pinfunction "3_3") (pintype "passive"))
      (node (ref "R19") (pin "1") (pinfunction "1_1") (pintype "passive"))
      (node (ref "U6") (pin "4") (pinfunction "D5_4") (pintype "input"))
    )
    (net (code "18") (name "BR7") (class "Default")
      (node (ref "D20") (pin "3") (pinfunction "3_3") (pintype "passive"))
      (node (ref "D21") (pin "3") (pinfunction "3_3") (pintype "passive"))
      (node (ref "D22") (pin "3") (pinfunction "3_3") (pintype "passive"))
      (node (ref "R20") (pin "1") (pinfunction "1_1") (pintype "passive"))
      (node (ref "U6") (pin "5") (pinfunction "D6_5") (pintype "input"))
    )
    (net (code "19") (name "BR8") (class "Default")
      (node (ref "D23") (pin "3") (pinfunction "3_3") (pintype "passive"))
      (node (ref "D24") (pin "3") (pinfunction "3_3") (pintype "passive"))
      (node (ref "D25") (pin "3") (pinfunction "3_3") (pintype "passive"))
      (node (ref "R21") (pin "1") (pinfunction "1_1") (pintype "passive"))
      (node (ref "U6") (pin "6") (pinfunction "D7_6") (pintype "input"))
    )
    (net (code "20") (name "BTLDR_BUTTON") (class "Default")
      (node (ref "R2") (pin "1") (pinfunction "1_1") (pintype "passive"))
      (node (ref "SW23") (pin "1") (pinfunction "1_1") (pintype "passive"))
      (node (ref "U5") (pin "24") (pinfunction "PC4_24") (pintype "bidirectional"))
    )
    (net (code "21") (name "D+") (class "Default")
      (node (ref "R4") (pin "1") (pinfunction "1_1") (pintype "passive"))
      (node (ref "U5") (pin "45") (pinfunction "PA12_45") (pintype "bidirectional"))
    )
    (net (code "22") (name "D+X") (class "Default")
      (node (ref "CONN1") (pin "D+") (pinfunction "D+_D+") (pintype "bidirectional"))
      (node (ref "D14") (pin "2") (pinfunction "I/O1_2") (pintype "passive"))
      (node (ref "R4") (pin "2") (pinfunction "2_2") (pintype "passive"))
    )
    (net (code "23") (name "D-") (class "Default")
      (node (ref "R5") (pin "1") (pinfunction "1_1") (pintype "passive"))
      (node (ref "U5") (pin "44") (pinfunction "PA11_44") (pintype "bidirectional"))
    )
    (net (code "24") (name "D-X") (class "Default")
      (node (ref "CONN1") (pin "D-") (pinfunction "D-_D-") (pintype "bidirectional"))
      (node (ref "D14") (pin "3") (pinfunction "I/O2_3") (pintype "passive"))
      (node (ref "R5") (pin "2") (pinfunction "2_2") (pintype "passive"))
    )
    (net (code "25") (name "DEC_IN_A0") (class "Default")
      (node (ref "U5") (pin "39") (pinfunction "PC8_39") (pintype "bidirectional"))
      (node (ref "U9") (pin "1") (pinfunction "A0_1") (pintype "input"))
    )
    (net (code "26") (name "DEC_IN_A1") (class "Default")
      (node (ref "U5") (pin "38") (pinfunction "PC7_38") (pintype "bidirectional"))
      (node (ref "U9") (pin "2") (pinfunction "A1_2") (pintype "input"))
    )
    (net (code "27") (name "DEC_IN_A2") (class "Default")
      (node (ref "U5") (pin "37") (pinfunction "PC6_37") (pintype "bidirectional"))
      (node (ref "U9") (pin "3") (pinfunction "A2_3") (pintype "input"))
    )
    (net (code "28") (name "DEC_OUT_A0") (class "Default")
      (node (ref "U5") (pin "62") (pinfunction "PB9_62") (pintype "bidirectional"))
      (node (ref "U7") (pin "1") (pinfunction "A0_1") (pintype "input"))
    )
    (net (code "29") (name "DEC_OUT_A1") (class "Default")
      (node (ref "U5") (pin "59") (pinfunction "PB7_59") (pintype "bidirectional"))
      (node (ref "U7") (pin "2") (pinfunction "A1_2") (pintype "input"))
    )
    (net (code "30") (name "DEC_OUT_A2") (class "Default")
      (node (ref "U5") (pin "58") (pinfunction "PB6_58") (pintype "bidirectional"))
      (node (ref "U7") (pin "3") (pinfunction "A2_3") (pintype "input"))
    )
    (net (code "31") (name "E1_A") (class "Default")
      (node (ref "D13") (pin "1") (pinfunction "1_1") (pintype "passive"))
      (node (ref "ENC1") (pin "A") (pinfunction "A_A") (pintype "output"))
    )
    (net (code "32") (name "E1_B") (class "Default")
      (node (ref "D17") (pin "1") (pinfunction "1_1") (pintype "passive"))
      (node (ref "ENC1") (pin "B") (pinfunction "B_B") (pintype "output"))
    )
    (net (code "33") (name "E2_A") (class "Default")
      (node (ref "D20") (pin "1") (pinfunction "1_1") (pintype "passive"))
      (node (ref "ENC2") (pin "A") (pinfunction "A_A") (pintype "output"))
    )
    (net (code "34") (name "E2_B") (class "Default")
      (node (ref "D23") (pin "1") (pinfunction "1_1") (pintype "passive"))
      (node (ref "ENC2") (pin "B") (pinfunction "B_B") (pintype "output"))
    )
    (net (code "35") (name "E3_A") (class "Default")
      (node (ref "D13") (pin "2") (pinfunction "2_2") (pintype "passive"))
      (node (ref "ENC3") (pin "A") (pinfunction "A_A") (pintype "output"))
    )
    (net (code "36") (name "E3_B") (class "Default")
      (node (ref "D17") (pin "2") (pinfunction "2_2") (pintype "passive"))
      (node (ref "ENC3") (pin "B") (pinfunction "B_B") (pintype "output"))
    )
    (net (code "37") (name "E4_A") (class "Default")
      (node (ref "D15") (pin "1") (pinfunction "1_1") (pintype "passive"))
      (node (ref "ENC4") (pin "A") (pinfunction "A_A") (pintype "output"))
    )
    (net (code "38") (name "E4_B") (class "Default")
      (node (ref "D18") (pin "1") (pinfunction "1_1") (pintype "passive"))
      (node (ref "ENC4") (pin "B") (pinfunction "B_B") (pintype "output"))
    )
    (net (code "39") (name "E5_A") (class "Default")
      (node (ref "D15") (pin "2") (pinfunction "2_2") (pintype "passive"))
      (node (ref "ENC5") (pin "A") (pinfunction "A_A") (pintype "output"))
    )
    (net (code "40") (name "E5_B") (class "Default")
      (node (ref "D18") (pin "2") (pinfunction "2_2") (pintype "passive"))
      (node (ref "ENC5") (pin "B") (pinfunction "B_B") (pintype "output"))
    )
    (net (code "41") (name "E6_A") (class "Default")
      (node (ref "D16") (pin "1") (pinfunction "1_1") (pintype "passive"))
      (node (ref "ENC6") (pin "A") (pinfunction "A_A") (pintype "output"))
    )
    (net (code "42") (name "E6_B") (class "Default")
      (node (ref "D19") (pin "1") (pinfunction "1_1") (pintype "passive"))
      (node (ref "ENC6") (pin "B") (pinfunction "B_B") (pintype "output"))
    )
    (net (code "43") (name "E7_A") (class "Default")
      (node (ref "D20") (pin "2") (pinfunction "2_2") (pintype "passive"))
      (node (ref "ENC7") (pin "A") (pinfunction "A_A") (pintype "output"))
    )
    (net (code "44") (name "E7_B") (class "Default")
      (node (ref "D23") (pin "2") (pinfunction "2_2") (pintype "passive"))
      (node (ref "ENC7") (pin "B") (pinfunction "B_B") (pintype "output"))
    )
    (net (code "45") (name "E8_A") (class "Default")
      (node (ref "D21") (pin "1") (pinfunction "1_1") (pintype "passive"))
      (node (ref "ENC8") (pin "A") (pinfunction "A_A") (pintype "output"))
    )
    (net (code "46") (name "E8_B") (class "Default")
      (node (ref "D24") (pin "1") (pinfunction "1_1") (pintype "passive"))
      (node (ref "ENC8") (pin "B") (pinfunction "B_B") (pintype "output"))
    )
    (net (code "47") (name "E9_A") (class "Default")
      (node (ref "D21") (pin "2") (pinfunction "2_2") (pintype "passive"))
      (node (ref "ENC9") (pin "A") (pinfunction "A_A") (pintype "output"))
    )
    (net (code "48") (name "E9_B") (class "Default")
      (node (ref "D24") (pin "2") (pinfunction "2_2") (pintype "passive"))
      (node (ref "ENC9") (pin "B") (pinfunction "B_B") (pintype "output"))
    )
    (net (code "49") (name "E10_A") (class "Default")
      (node (ref "D22") (pin "1") (pinfunction "1_1") (pintype "passive"))
      (node (ref "ENC10") (pin "A") (pinfunction "A_A") (pintype "output"))
    )
    (net (code "50") (name "E10_B") (class "Default")
      (node (ref "D25") (pin "1") (pinfunction "1_1") (pintype "passive"))
      (node (ref "ENC10") (pin "B") (pinfunction "B_B") (pintype "output"))
    )
    (net (code "51") (name "GND") (class "Default")
      (node (ref "C1") (pin "-") (pinfunction "-_-") (pintype "passive"))
      (node (ref "C10") (pin "2") (pinfunction "2_2") (pintype "passive"))
      (node (ref "C11") (pin "2") (pinfunction "2_2") (pintype "passive"))
      (node (ref "C12") (pin "2") (pinfunction "2_2") (pintype "passive"))
      (node (ref "C13") (pin "2") (pinfunction "2_2") (pintype "passive"))
      (node (ref "C14") (pin "2") (pinfunction "2_2") (pintype "passive"))
      (node (ref "C15") (pin "2") (pinfunction "2_2") (pintype "passive"))
      (node (ref "C16") (pin "2") (pinfunction "2_2") (pintype "passive"))
      (node (ref "C17") (pin "1") (pinfunction "1_1") (pintype "passive"))
      (node (ref "C18") (pin "1") (pinfunction "1_1") (pintype "passive"))
      (node (ref "C19") (pin "2") (pinfunction "2_2") (pintype "passive"))
      (node (ref "C2") (pin "2") (pinfunction "2_2") (pintype "passive"))
      (node (ref "C20") (pin "1") (pinfunction "1_1") (pintype "passive"))
      (node (ref "C21") (pin "1") (pinfunction "1_1") (pintype "passive"))
      (node (ref "C22") (pin "1") (pinfunction "1_1") (pintype "passive"))
      (node (ref "C23") (pin "2") (pinfunction "2_2") (pintype "passive"))
      (node (ref "C24") (pin "2") (pinfunction "2_2") (pintype "passive"))
      (node (ref "C25") (pin "2") (pinfunction "2_2") (pintype "passive"))
      (node (ref "C26") (pin "2") (pinfunction "2_2") (pintype "passive"))
      (node (ref "C27") (pin "2") (pinfunction "2_2") (pintype "passive"))
      (node (ref "C3") (pin "1") (pinfunction "1_1") (pintype "passive"))
      (node (ref "C4") (pin "2") (pinfunction "2_2") (pintype "passive"))
      (node (ref "C5") (pin "2") (pinfunction "2_2") (pintype "passive"))
      (node (ref "C6") (pin "2") (pinfunction "2_2") (pintype "passive"))
      (node (ref "C7") (pin "2") (pinfunction "2_2") (pintype "passive"))
      (node (ref "C8") (pin "2") (pinfunction "2_2") (pintype "passive"))
      (node (ref "C9") (pin "1") (pinfunction "1_1") (pintype "passive"))
      (node (ref "CONN1") (pin "GND") (pinfunction "GND_GND") (pintype "bidirectional"))
      (node (ref "CONN2") (pin "1") (pinfunction "SLEEVE_1") (pintype "passive"))
      (node (ref "CONN3") (pin "3") (pinfunction "3_3") (pintype "passive"))
      (node (ref "D14") (pin "1") (pinfunction "GND_1") (pintype "passive"))
      (node (ref "ENC1") (pin "S1") (pinfunction "S_S1") (pintype "passive"))
      (node (ref "ENC1") (pin "S2") (pinfunction "S_S2") (pintype "passive"))
      (node (ref "ENC10") (pin "S1") (pinfunction "S_S1") (pintype "passive"))
      (node (ref "ENC10") (pin "S2") (pinfunction "S_S2") (pintype "passive"))
      (node (ref "ENC2") (pin "S1") (pinfunction "S_S1") (pintype "passive"))
      (node (ref "ENC2") (pin "S2") (pinfunction "S_S2") (pintype "passive"))
      (node (ref "ENC3") (pin "S1") (pinfunction "S_S1") (pintype "passive"))
      (node (ref "ENC3") (pin "S2") (pinfunction "S_S2") (pintype "passive"))
      (node (ref "ENC4") (pin "S1") (pinfunction "S_S1") (pintype "passive"))
      (node (ref "ENC4") (pin "S2") (pinfunction "S_S2") (pintype "passive"))
      (node (ref "ENC5") (pin "S1") (pinfunction "S_S1") (pintype "passive"))
      (node (ref "ENC5") (pin "S2") (pinfunction "S_S2") (pintype "passive"))
      (node (ref "ENC6") (pin "S1") (pinfunction "S_S1") (pintype "passive"))
      (node (ref "ENC6") (pin "S2") (pinfunction "S_S2") (pintype "passive"))
      (node (ref "ENC7") (pin "S1") (pinfunction "S_S1") (pintype "passive"))
      (node (ref "ENC7") (pin "S2") (pinfunction "S_S2") (pintype "passive"))
      (node (ref "ENC8") (pin "S1") (pinfunction "S_S1") (pintype "passive"))
      (node (ref "ENC8") (pin "S2") (pinfunction "S_S2") (pintype "passive"))
      (node (ref "ENC9") (pin "S1") (pinfunction "S_S1") (pintype "passive"))
      (node (ref "ENC9") (pin "S2") (pinfunction "S_S2") (pintype "passive"))
      (node (ref "L1") (pin "2") (pinfunction "2_2") (pintype "passive"))
      (node (ref "LCD1") (pin "1") (pinfunction "GND_1") (pintype "power_in"))
      (node (ref "LCD1") (pin "10") (pinfunction "DB6_10") (pintype "input"))
      (node (ref "LCD1") (pin "11") (pinfunction "DB7_11") (pintype "input"))
      (node (ref "LCD1") (pin "12") (pinfunction "~{RD}_12") (pintype "input"))
      (node (ref "LCD1") (pin "13") (pinfunction "~{WR}_13") (pintype "input"))
      (node (ref "LCD1") (pin "6") (pinfunction "DB2_6") (pintype "input"))
      (node (ref "LCD1") (pin "7") (pinfunction "DB3_7") (pintype "input"))
      (node (ref "LCD1") (pin "8") (pinfunction "DB4_8") (pintype "input"))
      (node (ref "LCD1") (pin "9") (pinfunction "DB5_9") (pintype "input"))
      (node (ref "R1") (pin "2") (pinfunction "2_2") (pintype "passive"))
      (node (ref "SW23") (pin "2") (pinfunction "2_2") (pintype "passive"))
      (node (ref "U1") (pin "12") (pinfunction "GND_12") (pintype "passive"))
      (node (ref "U1") (pin "15") (pinfunction "~{E}_15") (pintype "input"))
      (node (ref "U1") (pin "16") (pinfunction "Y15_16") (pintype "bidirectional"))
      (node (ref "U1") (pin "17") (pinfunction "Y14_17") (pintype "bidirectional"))
      (node (ref "U1") (pin "18") (pinfunction "Y13_18") (pintype "bidirectional"))
      (node (ref "U1") (pin "19") (pinfunction "Y12_19") (pintype "bidirectional"))
      (node (ref "U1") (pin "20") (pinfunction "Y11_20") (pintype "bidirectional"))
      (node (ref "U1") (pin "21") (pinfunction "Y10_21") (pintype "bidirectional"))
      (node (ref "U1") (pin "22") (pinfunction "Y9_22") (pintype "bidirectional"))
      (node (ref "U2") (pin "12") (pinfunction "GND_12") (pintype "passive"))
      (node (ref "U2") (pin "15") (pinfunction "~{E}_15") (pintype "input"))
      (node (ref "U2") (pin "16") (pinfunction "Y15_16") (pintype "bidirectional"))
      (node (ref "U2") (pin "17") (pinfunction "Y14_17") (pintype "bidirectional"))
      (node (ref "U2") (pin "18") (pinfunction "Y13_18") (pintype "bidirectional"))
      (node (ref "U2") (pin "19") (pinfunction "Y12_19") (pintype "bidirectional"))
      (node (ref "U2") (pin "20") (pinfunction "Y11_20") (pintype "bidirectional"))
      (node (ref "U2") (pin "21") (pinfunction "Y10_21") (pintype "bidirectional"))
      (node (ref "U2") (pin "22") (pinfunction "Y9_22") (pintype "bidirectional"))
      (node (ref "U3") (pin "12") (pinfunction "GND_12") (pintype "passive"))
      (node (ref "U3") (pin "15") (pinfunction "~{E}_15") (pintype "input"))
      (node (ref "U3") (pin "16") (pinfunction "Y15_16") (pintype "bidirectional"))
      (node (ref "U3") (pin "17") (pinfunction "Y14_17") (pintype "bidirectional"))
      (node (ref "U3") (pin "18") (pinfunction "Y13_18") (pintype "bidirectional"))
      (node (ref "U3") (pin "19") (pinfunction "Y12_19") (pintype "bidirectional"))
      (node (ref "U3") (pin "20") (pinfunction "Y11_20") (pintype "bidirectional"))
      (node (ref "U3") (pin "21") (pinfunction "Y10_21") (pintype "bidirectional"))
      (node (ref "U3") (pin "22") (pinfunction "Y9_22") (pintype "bidirectional"))
      (node (ref "U4") (pin "12") (pinfunction "GND_12") (pintype "passive"))
      (node (ref "U4") (pin "15") (pinfunction "~{E}_15") (pintype "input"))
      (node (ref "U4") (pin "16") (pinfunction "Y15_16") (pintype "bidirectional"))
      (node (ref "U4") (pin "17") (pinfunction "Y14_17") (pintype "bidirectional"))
      (node (ref "U4") (pin "18") (pinfunction "Y13_18") (pintype "bidirectional"))
      (node (ref "U4") (pin "19") (pinfunction "Y12_19") (pintype "bidirectional"))
      (node (ref "U4") (pin "20") (pinfunction "Y11_20") (pintype "bidirectional"))
      (node (ref "U4") (pin "21") (pinfunction "Y10_21") (pintype "bidirectional"))
      (node (ref "U4") (pin "22") (pinfunction "Y9_22") (pintype "bidirectional"))
      (node (ref "U5") (pin "12") (pinfunction "VSSA_12") (pintype "bidirectional"))
      (node (ref "U5") (pin "18") (pinfunction "VSS_18") (pintype "bidirectional"))
      (node (ref "U5") (pin "63") (pinfunction "VSS_63") (pintype "bidirectional"))
      (node (ref "U6") (pin "15") (pinfunction "~{CE}_15") (pintype "input"))
      (node (ref "U6") (pin "8") (pinfunction "GND_8") (pintype "power_in"))
      (node (ref "U7") (pin "4") (pinfunction "~{E1}_4") (pintype "input"))
      (node (ref "U7") (pin "5") (pinfunction "~{E2}_5") (pintype "input"))
      (node (ref "U7") (pin "8") (pinfunction "GND_8") (pintype "power_in"))
      (node (ref "U8") (pin "9") (pinfunction "GND_9") (pintype "power_in"))
      (node (ref "U9") (pin "4") (pinfunction "~{E1}_4") (pintype "input"))
      (node (ref "U9") (pin "5") (pinfunction "~{E2}_5") (pintype "input"))
      (node (ref "U9") (pin "8") (pinfunction "GND_8") (pintype "power_in"))
      (node (ref "VR1") (pin "2") (pinfunction "GND_2") (pintype "power_in"))
      (node (ref "VR2") (pin "2") (pinfunction "GND_2") (pintype "passive"))
    )
    (net (code "52") (name "LCD_CS") (class "Default")
      (node (ref "LCD1") (pin "16") (pinfunction "~{CS}_16") (pintype "input"))
      (node (ref "U5") (pin "52") (pinfunction "PC11_52") (pintype "bidirectional"))
    )
    (net (code "53") (name "LCD_DC") (class "Default")
      (node (ref "LCD1") (pin "14") (pinfunction "DC_14") (pintype "input"))
      (node (ref "U5") (pin "54") (pinfunction "PD2_54") (pintype "bidirectional"))
    )
    (net (code "54") (name "LCD_RESET") (class "Default")
      (node (ref "LCD1") (pin "15") (pinfunction "~{RESET}_15") (pintype "input"))
      (node (ref "U5") (pin "50") (pinfunction "PA15_50") (pintype "bidirectional"))
    )
    (net (code "55") (name "LC_1") (class "Default")
      (node (ref "SW15") (pin "6-C") (pinfunction "C_6-C") (pintype "passive"))
      (node (ref "SW22") (pin "6-C") (pinfunction "C_6-C") (pintype "passive"))
      (node (ref "SW8") (pin "6-C") (pinfunction "C_6-C") (pintype "passive"))
      (node (ref "U8") (pin "18") (pinfunction "1C_18") (pintype "open_collector"))
    )
    (net (code "56") (name "LC_2") (class "Default")
      (node (ref "SW14") (pin "6-C") (pinfunction "C_6-C") (pintype "passive"))
      (node (ref "SW21") (pin "6-C") (pinfunction "C_6-C") (pintype "passive"))
      (node (ref "SW7") (pin "6-C") (pinfunction "C_6-C") (pintype "passive"))
      (node (ref "U8") (pin "17") (pinfunction "2C_17") (pintype "open_collector"))
    )
    (net (code "57") (name "LC_3") (class "Default")
      (node (ref "SW13") (pin "6-C") (pinfunction "C_6-C") (pintype "passive"))
      (node (ref "SW20") (pin "6-C") (pinfunction "C_6-C") (pintype "passive"))
      (node (ref "SW6") (pin "6-C") (pinfunction "C_6-C") (pintype "passive"))
      (node (ref "U8") (pin "16") (pinfunction "3C_16") (pintype "open_collector"))
    )
    (net (code "58") (name "LC_4") (class "Default")
      (node (ref "SW12") (pin "6-C") (pinfunction "C_6-C") (pintype "passive"))
      (node (ref "SW19") (pin "6-C") (pinfunction "C_6-C") (pintype "passive"))
      (node (ref "SW5") (pin "6-C") (pinfunction "C_6-C") (pintype "passive"))
      (node (ref "U8") (pin "15") (pinfunction "4C_15") (pintype "open_collector"))
    )
    (net (code "59") (name "LC_5") (class "Default")
      (node (ref "SW11") (pin "6-C") (pinfunction "C_6-C") (pintype "passive"))
      (node (ref "SW18") (pin "6-C") (pinfunction "C_6-C") (pintype "passive"))
      (node (ref "SW4") (pin "6-C") (pinfunction "C_6-C") (pintype "passive"))
      (node (ref "U8") (pin "14") (pinfunction "5C_14") (pintype "open_collector"))
    )
    (net (code "60") (name "LC_6") (class "Default")
      (node (ref "SW10") (pin "6-C") (pinfunction "C_6-C") (pintype "passive"))
      (node (ref "SW17") (pin "6-C") (pinfunction "C_6-C") (pintype "passive"))
      (node (ref "SW3") (pin "6-C") (pinfunction "C_6-C") (pintype "passive"))
      (node (ref "U8") (pin "13") (pinfunction "6C_13") (pintype "open_collector"))
    )
    (net (code "61") (name "LC_7") (class "Default")
      (node (ref "SW16") (pin "6-C") (pinfunction "C_6-C") (pintype "passive"))
      (node (ref "SW2") (pin "6-C") (pinfunction "C_6-C") (pintype "passive"))
      (node (ref "SW9") (pin "6-C") (pinfunction "C_6-C") (pintype "passive"))
      (node (ref "U8") (pin "12") (pinfunction "7C_12") (pintype "open_collector"))
    )
    (net (code "62") (name "LC_8") (class "Default")
      (node (ref "SW1") (pin "6-C") (pinfunction "C_6-C") (pintype "passive"))
      (node (ref "U8") (pin "11") (pinfunction "8C_11") (pintype "open_collector"))
    )
    (net (code "63") (name "LEDS_VCC") (class "Default")
      (node (ref "C14") (pin "1") (pinfunction "1_1") (pintype "passive"))
      (node (ref "Q1") (pin "2") (pinfunction "S2_2") (pintype "bidirectional"))
      (node (ref "Q1") (pin "5") (pinfunction "S1_5") (pintype "bidirectional"))
      (node (ref "Q2") (pin "2") (pinfunction "S2_2") (pintype "bidirectional"))
      (node (ref "R10") (pin "1") (pinfunction "1_1") (pintype "passive"))
      (node (ref "R12") (pin "1") (pinfunction "1_1") (pintype "passive"))
      (node (ref "R8") (pin "1") (pinfunction "1_1") (pintype "passive"))
      (node (ref "VR1") (pin "5") (pinfunction "OUT_5") (pintype "power_in"))
    )
    (net (code "64") (name "LR_1_MI") (class "Default")
      (node (ref "Q1") (pin "1") (pinfunction "G1_1") (pintype "bidirectional"))
      (node (ref "R8") (pin "2") (pinfunction "2_2") (pintype "passive"))
      (node (ref "U5") (pin "57") (pinfunction "PB5_57") (pintype "bidirectional"))
    )
    (net (code "65") (name "LR_1_MO") (class "Default")
      (node (ref "R9") (pin "2") (pinfunction "2_2") (pintype "passive"))
      (node (ref "SW1") (pin "6-A") (pinfunction "A_6-A") (pintype "passive"))
      (node (ref "SW2") (pin "6-A") (pinfunction "A_6-A") (pintype "passive"))
      (node (ref "SW3") (pin "6-A") (pinfunction "A_6-A") (pintype "passive"))
      (node (ref "SW4") (pin "6-A") (pinfunction "A_6-A") (pintype "passive"))
      (node (ref "SW5") (pin "6-A") (pinfunction "A_6-A") (pintype "passive"))
      (node (ref "SW6") (pin "6-A") (pinfunction "A_6-A") (pintype "passive"))
      (node (ref "SW7") (pin "6-A") (pinfunction "A_6-A") (pintype "passive"))
      (node (ref "SW8") (pin "6-A") (pinfunction "A_6-A") (pintype "passive"))
    )
    (net (code "66") (name "LR_2_MI") (class "Default")
      (node (ref "Q1") (pin "3") (pinfunction "G2_3") (pintype "bidirectional"))
      (node (ref "R10") (pin "2") (pinfunction "2_2") (pintype "passive"))
      (node (ref "U5") (pin "56") (pinfunction "PB4_56") (pintype "bidirectional"))
    )
    (net (code "67") (name "LR_2_MO") (class "Default")
      (node (ref "R11") (pin "2") (pinfunction "2_2") (pintype "passive"))
      (node (ref "SW10") (pin "6-A") (pinfunction "A_6-A") (pintype "passive"))
      (node (ref "SW11") (pin "6-A") (pinfunction "A_6-A") (pintype "passive"))
      (node (ref "SW12") (pin "6-A") (pinfunction "A_6-A") (pintype "passive"))
      (node (ref "SW13") (pin "6-A") (pinfunction "A_6-A") (pintype "passive"))
      (node (ref "SW14") (pin "6-A") (pinfunction "A_6-A") (pintype "passive"))
      (node (ref "SW15") (pin "6-A") (pinfunction "A_6-A") (pintype "passive"))
      (node (ref "SW9") (pin "6-A") (pinfunction "A_6-A") (pintype "passive"))
    )
    (net (code "68") (name "LR_3_MI") (class "Default")
      (node (ref "Q2") (pin "3") (pinfunction "G2_3") (pintype "bidirectional"))
      (node (ref "R12") (pin "2") (pinfunction "2_2") (pintype "passive"))
      (node (ref "U5") (pin "55") (pinfunction "PB3_55") (pintype "bidirectional"))
    )
    (net (code "69") (name "LR_3_MO") (class "Default")
      (node (ref "R13") (pin "2") (pinfunction "2_2") (pintype "passive"))
      (node (ref "SW16") (pin "6-A") (pinfunction "A_6-A") (pintype "passive"))
      (node (ref "SW17") (pin "6-A") (pinfunction "A_6-A") (pintype "passive"))
      (node (ref "SW18") (pin "6-A") (pinfunction "A_6-A") (pintype "passive"))
      (node (ref "SW19") (pin "6-A") (pinfunction "A_6-A") (pintype "passive"))
      (node (ref "SW20") (pin "6-A") (pinfunction "A_6-A") (pintype "passive"))
      (node (ref "SW21") (pin "6-A") (pinfunction "A_6-A") (pintype "passive"))
      (node (ref "SW22") (pin "6-A") (pinfunction "A_6-A") (pintype "passive"))
    )
    (net (code "70") (name "MIDI_OUT") (class "Default")
      (node (ref "R6") (pin "2") (pinfunction "2_2") (pintype "passive"))
      (node (ref "U5") (pin "29") (pinfunction "PB10_29") (pintype "bidirectional"))
    )
    (net (code "71") (name "MOSI") (class "Default")
      (node (ref "LCD1") (pin "5") (pinfunction "DB1/MOSI_5") (pintype "input"))
      (node (ref "U5") (pin "53") (pinfunction "PC12_53") (pintype "bidirectional"))
    )
    (net (code "72") (name "MUX_COMMON_1") (class "Default")
      (node (ref "U1") (pin "1") (pinfunction "Z_1") (pintype "bidirectional"))
      (node (ref "U5") (pin "17") (pinfunction "PA3_17") (pintype "bidirectional"))
    )
    (net (code "73") (name "MUX_COMMON_2") (class "Default")
      (node (ref "U2") (pin "1") (pinfunction "Z_1") (pintype "bidirectional"))
      (node (ref "U5") (pin "14") (pinfunction "PA0_14") (pintype "bidirectional"))
    )
    (net (code "74") (name "MUX_COMMON_3") (class "Default")
      (node (ref "U3") (pin "1") (pinfunction "Z_1") (pintype "bidirectional"))
      (node (ref "U5") (pin "15") (pinfunction "PA1_15") (pintype "bidirectional"))
    )
    (net (code "75") (name "MUX_COMMON_4") (class "Default")
      (node (ref "U4") (pin "1") (pinfunction "Z_1") (pintype "bidirectional"))
      (node (ref "U5") (pin "16") (pinfunction "PA2_16") (pintype "bidirectional"))
    )
    (net (code "76") (name "MUX_S0") (class "Default")
      (node (ref "U1") (pin "10") (pinfunction "S0_10") (pintype "input"))
      (node (ref "U2") (pin "10") (pinfunction "S0_10") (pintype "input"))
      (node (ref "U3") (pin "10") (pinfunction "S0_10") (pintype "input"))
      (node (ref "U4") (pin "10") (pinfunction "S0_10") (pintype "input"))
      (node (ref "U5") (pin "33") (pinfunction "PB12_33") (pintype "bidirectional"))
    )
    (net (code "77") (name "MUX_S1") (class "Default")
      (node (ref "U1") (pin "11") (pinfunction "S1_11") (pintype "input"))
      (node (ref "U2") (pin "11") (pinfunction "S1_11") (pintype "input"))
      (node (ref "U3") (pin "11") (pinfunction "S1_11") (pintype "input"))
      (node (ref "U4") (pin "11") (pinfunction "S1_11") (pintype "input"))
      (node (ref "U5") (pin "34") (pinfunction "PB13_34") (pintype "bidirectional"))
    )
    (net (code "78") (name "MUX_S2") (class "Default")
      (node (ref "U1") (pin "14") (pinfunction "S2_14") (pintype "input"))
      (node (ref "U2") (pin "14") (pinfunction "S2_14") (pintype "input"))
      (node (ref "U3") (pin "14") (pinfunction "S2_14") (pintype "input"))
      (node (ref "U4") (pin "14") (pinfunction "S2_14") (pintype "input"))
      (node (ref "U5") (pin "36") (pinfunction "PB15_36") (pintype "bidirectional"))
    )
    (net (code "79") (name "MUX_S3") (class "Default")
      (node (ref "U1") (pin "13") (pinfunction "S3_13") (pintype "input"))
      (node (ref "U2") (pin "13") (pinfunction "S3_13") (pintype "input"))
      (node (ref "U3") (pin "13") (pinfunction "S3_13") (pintype "input"))
      (node (ref "U4") (pin "13") (pinfunction "S3_13") (pintype "input"))
      (node (ref "U5") (pin "35") (pinfunction "PB14_35") (pintype "bidirectional"))
    )
    (net (code "80") (name "NRST") (class "Default")
      (node (ref "C27") (pin "1") (pinfunction "1_1") (pintype "passive"))
      (node (ref "U5") (pin "7") (pinfunction "NRST_7") (pintype "bidirectional"))
    )
    (net (code "81") (name "Net-(C3-Pad2)") (class "Default")
      (node (ref "C3") (pin "2") (pinfunction "2_2") (pintype "passive"))
      (node (ref "U5") (pin "31") (pinfunction "VCAP_31") (pintype "bidirectional"))
    )
    (net (code "82") (name "Net-(C6-Pad1)") (class "Default")
      (node (ref "C6") (pin "1") (pinfunction "1_1") (pintype "passive"))
      (node (ref "U5") (pin "47") (pinfunction "VCAP_47") (pintype "bidirectional"))
    )
    (net (code "83") (name "Net-(CONN1A-S)") (class "Default")
      (node (ref "CONN1") (pin "S1") (pinfunction "S_S1") (pintype "passive"))
      (node (ref "CONN1") (pin "S2") (pinfunction "S_S2") (pintype "passive"))
      (node (ref "L1") (pin "1") (pinfunction "1_1") (pintype "passive"))
    )
    (net (code "84") (name "Net-(CONN2-RING)") (class "Default")
      (node (ref "CONN2") (pin "3") (pinfunction "RING_3") (pintype "passive"))
      (node (ref "R6") (pin "1") (pinfunction "1_1") (pintype "passive"))
    )
    (net (code "85") (name "Net-(CONN2-TIP)") (class "Default")
      (node (ref "CONN2") (pin "2") (pinfunction "TIP_2") (pintype "passive"))
      (node (ref "R7") (pin "1") (pinfunction "1_1") (pintype "passive"))
    )
    (net (code "86") (name "Net-(ENC1D-2)") (class "Default")
      (node (ref "D5") (pin "2") (pinfunction "2_2") (pintype "passive"))
      (node (ref "ENC1") (pin "E") (pinfunction "2_E") (pintype "passive"))
    )
    (net (code "87") (name "Net-(ENC2D-2)") (class "Default")
      (node (ref "D9") (pin "2") (pinfunction "2_2") (pintype "passive"))
      (node (ref "ENC2") (pin "E") (pinfunction "2_E") (pintype "passive"))
    )
    (net (code "88") (name "Net-(Q1-D1)") (class "Default")
      (node (ref "Q1") (pin "6") (pinfunction "D1_6") (pintype "bidirectional"))
      (node (ref "R9") (pin "1") (pinfunction "1_1") (pintype "passive"))
    )
    (net (code "89") (name "Net-(Q1-D2)") (class "Default")
      (node (ref "Q1") (pin "4") (pinfunction "D2_4") (pintype "bidirectional"))
      (node (ref "R11") (pin "1") (pinfunction "1_1") (pintype "passive"))
    )
    (net (code "90") (name "Net-(Q2-D2)") (class "Default")
      (node (ref "Q2") (pin "4") (pinfunction "D2_4") (pintype "bidirectional"))
      (node (ref "R13") (pin "1") (pinfunction "1_1") (pintype "passive"))
    )
    (net (code "91") (name "Net-(SW1B-2)") (class "Default")
      (node (ref "D1") (pin "1") (pinfunction "1_1") (pintype "passive"))
      (node (ref "SW1") (pin "3") (pinfunction "2_3") (pintype "passive"))
    )
    (net (code "92") (name "Net-(SW2B-2)") (class "Default")
      (node (ref "D2") (pin "2") (pinfunction "2_2") (pintype "passive"))
      (node (ref "SW2") (pin "3") (pinfunction "2_3") (pintype "passive"))
    )
    (net (code "93") (name "Net-(SW3B-2)") (class "Default")
      (node (ref "D1") (pin "2") (pinfunction "2_2") (pintype "passive"))
      (node (ref "SW3") (pin "3") (pinfunction "2_3") (pintype "passive"))
    )
    (net (code "94") (name "Net-(SW4B-2)") (class "Default")
      (node (ref "D2") (pin "1") (pinfunction "1_1") (pintype "passive"))
      (node (ref "SW4") (pin "3") (pinfunction "2_3") (pintype "passive"))
    )
    (net (code "95") (name "Net-(SW5B-2)") (class "Default")
      (node (ref "D3") (pin "2") (pinfunction "2_2") (pintype "passive"))
      (node (ref "SW5") (pin "3") (pinfunction "2_3") (pintype "passive"))
    )
    (net (code "96") (name "Net-(SW6B-2)") (class "Default")
      (node (ref "D3") (pin "1") (pinfunction "1_1") (pintype "passive"))
      (node (ref "SW6") (pin "3") (pinfunction "2_3") (pintype "passive"))
    )
    (net (code "97") (name "Net-(SW7B-2)") (class "Default")
      (node (ref "D4") (pin "2") (pinfunction "2_2") (pintype "passive"))
      (node (ref "SW7") (pin "3") (pinfunction "2_3") (pintype "passive"))
    )
    (net (code "98") (name "Net-(SW8B-2)") (class "Default")
      (node (ref "D4") (pin "1") (pinfunction "1_1") (pintype "passive"))
      (node (ref "SW8") (pin "3") (pinfunction "2_3") (pintype "passive"))
    )
    (net (code "99") (name "Net-(SW9B-2)") (class "Default")
      (node (ref "D5") (pin "1") (pinfunction "1_1") (pintype "passive"))
      (node (ref "SW9") (pin "3") (pinfunction "2_3") (pintype "passive"))
    )
    (net (code "100") (name "Net-(SW10B-2)") (class "Default")
      (node (ref "D6") (pin "2") (pinfunction "2_2") (pintype "passive"))
      (node (ref "SW10") (pin "3") (pinfunction "2_3") (pintype "passive"))
    )
    (net (code "101") (name "Net-(SW11B-2)") (class "Default")
      (node (ref "D6") (pin "1") (pinfunction "1_1") (pintype "passive"))
      (node (ref "SW11") (pin "3") (pinfunction "2_3") (pintype "passive"))
    )
    (net (code "102") (name "Net-(SW12B-2)") (class "Default")
      (node (ref "D7") (pin "1") (pinfunction "1_1") (pintype "passive"))
      (node (ref "SW12") (pin "3") (pinfunction "2_3") (pintype "passive"))
    )
    (net (code "103") (name "Net-(SW13B-2)") (class "Default")
      (node (ref "D7") (pin "2") (pinfunction "2_2") (pintype "passive"))
      (node (ref "SW13") (pin "3") (pinfunction "2_3") (pintype "passive"))
    )
    (net (code "104") (name "Net-(SW14B-2)") (class "Default")
      (node (ref "D8") (pin "2") (pinfunction "2_2") (pintype "passive"))
      (node (ref "SW14") (pin "3") (pinfunction "2_3") (pintype "passive"))
    )
    (net (code "105") (name "Net-(SW15B-2)") (class "Default")
      (node (ref "D8") (pin "1") (pinfunction "1_1") (pintype "passive"))
      (node (ref "SW15") (pin "3") (pinfunction "2_3") (pintype "passive"))
    )
    (net (code "106") (name "Net-(SW16B-2)") (class "Default")
      (node (ref "D9") (pin "1") (pinfunction "1_1") (pintype "passive"))
      (node (ref "SW16") (pin "3") (pinfunction "2_3") (pintype "passive"))
    )
    (net (code "107") (name "Net-(SW17B-2)") (class "Default")
      (node (ref "D10") (pin "2") (pinfunction "2_2") (pintype "passive"))
      (node (ref "SW17") (pin "3") (pinfunction "2_3") (pintype "passive"))
    )
    (net (code "108") (name "Net-(SW18B-2)") (class "Default")
      (node (ref "D10") (pin "1") (pinfunction "1_1") (pintype "passive"))
      (node (ref "SW18") (pin "3") (pinfunction "2_3") (pintype "passive"))
    )
    (net (code "109") (name "Net-(SW19B-2)") (class "Default")
      (node (ref "D11") (pin "2") (pinfunction "2_2") (pintype "passive"))
      (node (ref "SW19") (pin "3") (pinfunction "2_3") (pintype "passive"))
    )
    (net (code "110") (name "Net-(SW20B-2)") (class "Default")
      (node (ref "D11") (pin "1") (pinfunction "1_1") (pintype "passive"))
      (node (ref "SW20") (pin "3") (pinfunction "2_3") (pintype "passive"))
    )
    (net (code "111") (name "Net-(SW21B-2)") (class "Default")
      (node (ref "D12") (pin "2") (pinfunction "2_2") (pintype "passive"))
      (node (ref "SW21") (pin "3") (pinfunction "2_3") (pintype "passive"))
    )
    (net (code "112") (name "Net-(SW22B-2)") (class "Default")
      (node (ref "D12") (pin "1") (pinfunction "1_1") (pintype "passive"))
      (node (ref "SW22") (pin "3") (pinfunction "2_3") (pintype "passive"))
    )
    (net (code "113") (name "Net-(U7-Y0)") (class "Default")
      (node (ref "U7") (pin "15") (pinfunction "Y0_15") (pintype "output"))
      (node (ref "U8") (pin "1") (pinfunction "1B_1") (pintype "input"))
    )
    (net (code "114") (name "Net-(U7-Y1)") (class "Default")
      (node (ref "U7") (pin "14") (pinfunction "Y1_14") (pintype "output"))
      (node (ref "U8") (pin "2") (pinfunction "2B_2") (pintype "input"))
    )
    (net (code "115") (name "Net-(U7-Y2)") (class "Default")
      (node (ref "U7") (pin "13") (pinfunction "Y2_13") (pintype "output"))
      (node (ref "U8") (pin "3") (pinfunction "3B_3") (pintype "input"))
    )
    (net (code "116") (name "Net-(U7-Y3)") (class "Default")
      (node (ref "U7") (pin "12") (pinfunction "Y3_12") (pintype "output"))
      (node (ref "U8") (pin "4") (pinfunction "4B_4") (pintype "input"))
    )
    (net (code "117") (name "Net-(U7-Y4)") (class "Default")
      (node (ref "U7") (pin "11") (pinfunction "Y4_11") (pintype "output"))
      (node (ref "U8") (pin "5") (pinfunction "5B_5") (pintype "input"))
    )
    (net (code "118") (name "Net-(U7-Y5)") (class "Default")
      (node (ref "U7") (pin "10") (pinfunction "Y5_10") (pintype "output"))
      (node (ref "U8") (pin "6") (pinfunction "6B_6") (pintype "input"))
    )
    (net (code "119") (name "Net-(U7-Y6)") (class "Default")
      (node (ref "U7") (pin "9") (pinfunction "Y6_9") (pintype "output"))
      (node (ref "U8") (pin "7") (pinfunction "7B_7") (pintype "input"))
    )
    (net (code "120") (name "Net-(U7-Y7)") (class "Default")
      (node (ref "U7") (pin "7") (pinfunction "Y7_7") (pintype "output"))
      (node (ref "U8") (pin "8") (pinfunction "8B_8") (pintype "input"))
    )
    (net (code "121") (name "OSC_IN") (class "Default")
      (node (ref "C25") (pin "1") (pinfunction "1_1") (pintype "passive"))
      (node (ref "U5") (pin "5") (pinfunction "PH0_5") (pintype "bidirectional"))
      (node (ref "Y1") (pin "1") (pinfunction "1_1") (pintype "passive"))
    )
    (net (code "122") (name "OSC_OUT") (class "Default")
      (node (ref "C26") (pin "1") (pinfunction "1_1") (pintype "passive"))
      (node (ref "U5") (pin "6") (pinfunction "PH1_6") (pintype "bidirectional"))
      (node (ref "Y1") (pin "2") (pinfunction "2_2") (pintype "passive"))
    )
    (net (code "123") (name "PAD_1_PIN_1") (class "Default")
      (node (ref "CONN4") (pin "18") (pinfunction "18_18") (pintype "passive"))
      (node (ref "U1") (pin "9") (pinfunction "Y0_9") (pintype "bidirectional"))
    )
    (net (code "124") (name "PAD_1_PIN_2") (class "Default")
      (node (ref "CONN4") (pin "13") (pinfunction "13_13") (pintype "passive"))
      (node (ref "U2") (pin "9") (pinfunction "Y0_9") (pintype "bidirectional"))
    )
    (net (code "125") (name "PAD_1_PIN_3") (class "Default")
      (node (ref "CONN5") (pin "2") (pinfunction "2_2") (pintype "passive"))
      (node (ref "U3") (pin "9") (pinfunction "Y0_9") (pintype "bidirectional"))
    )
    (net (code "126") (name "PAD_1_PIN_4") (class "Default")
      (node (ref "CONN5") (pin "1") (pinfunction "1_1") (pintype "passive"))
      (node (ref "U4") (pin "9") (pinfunction "Y0_9") (pintype "bidirectional"))
    )
    (net (code "127") (name "PAD_2_PIN_1") (class "Default")
      (node (ref "CONN4") (pin "12") (pinfunction "12_12") (pintype "passive"))
      (node (ref "U1") (pin "8") (pinfunction "Y1_8") (pintype "bidirectional"))
    )
    (net (code "128") (name "PAD_2_PIN_2") (class "Default")
      (node (ref "CONN4") (pin "7") (pinfunction "7_7") (pintype "passive"))
      (node (ref "U2") (pin "8") (pinfunction "Y1_8") (pintype "bidirectional"))
    )
    (net (code "129") (name "PAD_2_PIN_3") (class "Default")
      (node (ref "CONN5") (pin "8") (pinfunction "8_8") (pintype "passive"))
      (node (ref "U3") (pin "8") (pinfunction "Y1_8") (pintype "bidirectional"))
    )
    (net (code "130") (name "PAD_2_PIN_4") (class "Default")
      (node (ref "CONN5") (pin "7") (pinfunction "7_7") (pintype "passive"))
      (node (ref "U4") (pin "8") (pinfunction "Y1_8") (pintype "bidirectional"))
    )
    (net (code "131") (name "PAD_3_PIN_1") (class "Default")
      (node (ref "CONN4") (pin "6") (pinfunction "6_6") (pintype "passive"))
      (node (ref "U1") (pin "7") (pinfunction "Y2_7") (pintype "bidirectional"))
    )
    (net (code "132") (name "PAD_3_PIN_2") (class "Default")
      (node (ref "CONN4") (pin "1") (pinfunction "1_1") (pintype "passive"))
      (node (ref "U2") (pin "7") (pinfunction "Y2_7") (pintype "bidirectional"))
    )
    (net (code "133") (name "PAD_3_PIN_3") (class "Default")
      (node (ref "CONN5") (pin "14") (pinfunction "14_14") (pintype "passive"))
      (node (ref "U3") (pin "7") (pinfunction "Y2_7") (pintype "bidirectional"))
    )
    (net (code "134") (name "PAD_3_PIN_4") (class "Default")
      (node (ref "CONN5") (pin "13") (pinfunction "13_13") (pintype "passive"))
      (node (ref "U4") (pin "7") (pinfunction "Y2_7") (pintype "bidirectional"))
    )
    (net (code "135") (name "PAD_4_PIN_1") (class "Default")
      (node (ref "CONN4") (pin "17") (pinfunction "17_17") (pintype "passive"))
      (node (ref "U1") (pin "6") (pinfunction "Y3_6") (pintype "bidirectional"))
    )
    (net (code "136") (name "PAD_4_PIN_2") (class "Default")
      (node (ref "CONN4") (pin "14") (pinfunction "14_14") (pintype "passive"))
      (node (ref "U2") (pin "6") (pinfunction "Y3_6") (pintype "bidirectional"))
    )
    (net (code "137") (name "PAD_4_PIN_3") (class "Default")
      (node (ref "CONN5") (pin "4") (pinfunction "4_4") (pintype "passive"))
      (node (ref "U3") (pin "6") (pinfunction "Y3_6") (pintype "bidirectional"))
    )
    (net (code "138") (name "PAD_4_PIN_4") (class "Default")
      (node (ref "CONN5") (pin "3") (pinfunction "3_3") (pintype "passive"))
      (node (ref "U4") (pin "6") (pinfunction "Y3_6") (pintype "bidirectional"))
    )
    (net (code "139") (name "PAD_5_PIN_1") (class "Default")
      (node (ref "CONN4") (pin "11") (pinfunction "11_11") (pintype "passive"))
      (node (ref "U1") (pin "5") (pinfunction "Y4_5") (pintype "bidirectional"))
    )
    (net (code "140") (name "PAD_5_PIN_2") (class "Default")
      (node (ref "CONN4") (pin "8") (pinfunction "8_8") (pintype "passive"))
      (node (ref "U2") (pin "5") (pinfunction "Y4_5") (pintype "bidirectional"))
    )
    (net (code "141") (name "PAD_5_PIN_3") (class "Default")
      (node (ref "CONN5") (pin "10") (pinfunction "10_10") (pintype "passive"))
      (node (ref "U3") (pin "5") (pinfunction "Y4_5") (pintype "bidirectional"))
    )
    (net (code "142") (name "PAD_5_PIN_4") (class "Default")
      (node (ref "CONN5") (pin "9") (pinfunction "9_9") (pintype "passive"))
      (node (ref "U4") (pin "5") (pinfunction "Y4_5") (pintype "bidirectional"))
    )
    (net (code "143") (name "PAD_6_PIN_1") (class "Default")
      (node (ref "CONN4") (pin "5") (pinfunction "5_5") (pintype "passive"))
      (node (ref "U1") (pin "4") (pinfunction "Y5_4") (pintype "bidirectional"))
    )
    (net (code "144") (name "PAD_6_PIN_2") (class "Default")
      (node (ref "CONN4") (pin "2") (pinfunction "2_2") (pintype "passive"))
      (node (ref "U2") (pin "4") (pinfunction "Y5_4") (pintype "bidirectional"))
    )
    (net (code "145") (name "PAD_6_PIN_3") (class "Default")
      (node (ref "CONN5") (pin "16") (pinfunction "16_16") (pintype "passive"))
      (node (ref "U3") (pin "4") (pinfunction "Y5_4") (pintype "bidirectional"))
    )
    (net (code "146") (name "PAD_6_PIN_4") (class "Default")
      (node (ref "CONN5") (pin "15") (pinfunction "15_15") (pintype "passive"))
      (node (ref "U4") (pin "4") (pinfunction "Y5_4") (pintype "bidirectional"))
    )
    (net (code "147") (name "PAD_7_PIN_1") (class "Default")
      (node (ref "CONN4") (pin "16") (pinfunction "16_16") (pintype "passive"))
      (node (ref "U1") (pin "3") (pinfunction "Y6_3") (pintype "bidirectional"))
    )
    (net (code "148") (name "PAD_7_PIN_2") (class "Default")
      (node (ref "CONN4") (pin "15") (pinfunction "15_15") (pintype "passive"))
      (node (ref "U2") (pin "3") (pinfunction "Y6_3") (pintype "bidirectional"))
    )
    (net (code "149") (name "PAD_7_PIN_3") (class "Default")
      (node (ref "CONN5") (pin "6") (pinfunction "6_6") (pintype "passive"))
      (node (ref "U3") (pin "3") (pinfunction "Y6_3") (pintype "bidirectional"))
    )
    (net (code "150") (name "PAD_7_PIN_4") (class "Default")
      (node (ref "CONN5") (pin "5") (pinfunction "5_5") (pintype "passive"))
      (node (ref "U4") (pin "3") (pinfunction "Y6_3") (pintype "bidirectional"))
    )
    (net (code "151") (name "PAD_8_PIN_1") (class "Default")
      (node (ref "CONN4") (pin "10") (pinfunction "10_10") (pintype "passive"))
      (node (ref "U1") (pin "2") (pinfunction "Y7_2") (pintype "bidirectional"))
    )
    (net (code "152") (name "PAD_8_PIN_2") (class "Default")
      (node (ref "CONN4") (pin "9") (pinfunction "9_9") (pintype "passive"))
      (node (ref "U2") (pin "2") (pinfunction "Y7_2") (pintype "bidirectional"))
    )
    (net (code "153") (name "PAD_8_PIN_3") (class "Default")
      (node (ref "CONN5") (pin "12") (pinfunction "12_12") (pintype "passive"))
      (node (ref "U3") (pin "2") (pinfunction "Y7_2") (pintype "bidirectional"))
    )
    (net (code "154") (name "PAD_8_PIN_4") (class "Default")
      (node (ref "CONN5") (pin "11") (pinfunction "11_11") (pintype "passive"))
      (node (ref "U4") (pin "2") (pinfunction "Y7_2") (pintype "bidirectional"))
    )
    (net (code "155") (name "PAD_9_PIN_1") (class "Default")
      (node (ref "CONN4") (pin "4") (pinfunction "4_4") (pintype "passive"))
      (node (ref "U1") (pin "23") (pinfunction "Y8_23") (pintype "bidirectional"))
    )
    (net (code "156") (name "PAD_9_PIN_2") (class "Default")
      (node (ref "CONN4") (pin "3") (pinfunction "3_3") (pintype "passive"))
      (node (ref "U2") (pin "23") (pinfunction "Y8_23") (pintype "bidirectional"))
    )
    (net (code "157") (name "PAD_9_PIN_3") (class "Default")
      (node (ref "CONN5") (pin "18") (pinfunction "18_18") (pintype "passive"))
      (node (ref "U3") (pin "23") (pinfunction "Y8_23") (pintype "bidirectional"))
    )
    (net (code "158") (name "PAD_9_PIN_4") (class "Default")
      (node (ref "CONN5") (pin "17") (pinfunction "17_17") (pintype "passive"))
      (node (ref "U4") (pin "23") (pinfunction "Y8_23") (pintype "bidirectional"))
    )
    (net (code "159") (name "SCLK") (class "Default")
      (node (ref "LCD1") (pin "4") (pinfunction "DB0/SCLK_4") (pintype "input"))
      (node (ref "U5") (pin "51") (pinfunction "PC10_51") (pintype "bidirectional"))
    )
    (net (code "160") (name "SR_IN_CLOCK") (class "Default")
      (node (ref "U5") (pin "4") (pinfunction "PC15_4") (pintype "bidirectional"))
      (node (ref "U6") (pin "2") (pinfunction "CP_2") (pintype "bidirectional"))
    )
    (net (code "161") (name "SR_IN_DATA") (class "Default")
      (node (ref "U5") (pin "3") (pinfunction "PC14_3") (pintype "bidirectional"))
      (node (ref "U6") (pin "9") (pinfunction "Q7_9") (pintype "output"))
    )
    (net (code "162") (name "SR_IN_LATCH") (class "Default")
      (node (ref "U5") (pin "2") (pinfunction "PC13_2") (pintype "bidirectional"))
      (node (ref "U6") (pin "1") (pinfunction "~{PL}_1") (pintype "input"))
    )
    (net (code "163") (name "SWDCLK") (class "Default")
      (node (ref "CONN3") (pin "1") (pinfunction "1_1") (pintype "passive"))
      (node (ref "U5") (pin "49") (pinfunction "PA14_49") (pintype "bidirectional"))
    )
    (net (code "164") (name "SWDIO") (class "Default")
      (node (ref "CONN3") (pin "2") (pinfunction "2_2") (pintype "passive"))
      (node (ref "U5") (pin "46") (pinfunction "PA13_46") (pintype "bidirectional"))
    )
    (net (code "165") (name "unconnected-(D16-Pad2)") (class "Default")
      (node (ref "D16") (pin "2") (pinfunction "2_2") (pintype "passive"))
    )
    (net (code "166") (name "unconnected-(D19-Pad2)") (class "Default")
      (node (ref "D19") (pin "2") (pinfunction "2_2") (pintype "passive"))
    )
    (net (code "167") (name "unconnected-(D22-Pad2)") (class "Default")
      (node (ref "D22") (pin "2") (pinfunction "2_2") (pintype "passive"))
    )
    (net (code "168") (name "unconnected-(D25-Pad2)") (class "Default")
      (node (ref "D25") (pin "2") (pinfunction "2_2") (pintype "passive"))
    )
    (net (code "169") (name "unconnected-(LCD1-NC-Pad3)") (class "Default")
      (node (ref "LCD1") (pin "3") (pinfunction "NC_3") (pintype "no_connect"))
    )
    (net (code "170") (name "unconnected-(Q2-D1-Pad6)") (class "Default")
      (node (ref "Q2") (pin "6") (pinfunction "D1_6") (pintype "bidirectional"))
    )
    (net (code "171") (name "unconnected-(Q2-G1-Pad1)") (class "Default")
      (node (ref "Q2") (pin "1") (pinfunction "G1_1") (pintype "bidirectional"))
    )
    (net (code "172") (name "unconnected-(Q2-S1-Pad5)") (class "Default")
      (node (ref "Q2") (pin "5") (pinfunction "S1_5") (pintype "bidirectional"))
    )
    (net (code "173") (name "unconnected-(U5-PA4-Pad20)") (class "Default")
      (node (ref "U5") (pin "20") (pinfunction "PA4_20") (pintype "bidirectional"))
    )
    (net (code "174") (name "unconnected-(U5-PA5-Pad21)") (class "Default")
      (node (ref "U5") (pin "21") (pinfunction "PA5_21") (pintype "bidirectional"))
    )
    (net (code "175") (name "unconnected-(U5-PA6-Pad22)") (class "Default")
      (node (ref "U5") (pin "22") (pinfunction "PA6_22") (pintype "bidirectional"))
    )
    (net (code "176") (name "unconnected-(U5-PA7-Pad23)") (class "Default")
      (node (ref "U5") (pin "23") (pinfunction "PA7_23") (pintype "bidirectional"))
    )
    (net (code "177") (name "unconnected-(U5-PA8-Pad41)") (class "Default")
      (node (ref "U5") (pin "41") (pinfunction "PA8_41") (pintype "bidirectional"))
    )
    (net (code "178") (name "unconnected-(U5-PA9-Pad42)") (class "Default")
      (node (ref "U5") (pin "42") (pinfunction "PA9_42") (pintype "bidirectional"))
    )
    (net (code "179") (name "unconnected-(U5-PA10-Pad43)") (class "Default")
      (node (ref "U5") (pin "43") (pinfunction "PA10_43") (pintype "bidirectional"))
    )
    (net (code "180") (name "unconnected-(U5-PB0-Pad26)") (class "Default")
      (node (ref "U5") (pin "26") (pinfunction "PB0_26") (pintype "bidirectional"))
    )
    (net (code "181") (name "unconnected-(U5-PB1-Pad27)") (class "Default")
      (node (ref "U5") (pin "27") (pinfunction "PB1_27") (pintype "bidirectional"))
    )
    (net (code "182") (name "unconnected-(U5-PB2-Pad28)") (class "Default")
      (node (ref "U5") (pin "28") (pinfunction "PB2_28") (pintype "bidirectional"))
    )
    (net (code "183") (name "unconnected-(U5-PB8-Pad61)") (class "Default")
      (node (ref "U5") (pin "61") (pinfunction "PB8_61") (pintype "bidirectional"))
    )
    (net (code "184") (name "unconnected-(U5-PB11-Pad30)") (class "Default")
      (node (ref "U5") (pin "30") (pinfunction "PB11_30") (pintype "bidirectional"))
    )
    (net (code "185") (name "unconnected-(U5-PC0-Pad8)") (class "Default")
      (node (ref "U5") (pin "8") (pinfunction "PC0_8") (pintype "bidirectional"))
    )
    (net (code "186") (name "unconnected-(U5-PC1-Pad9)") (class "Default")
      (node (ref "U5") (pin "9") (pinfunction "PC1_9") (pintype "bidirectional"))
    )
    (net (code "187") (name "unconnected-(U5-PC2-Pad10)") (class "Default")
      (node (ref "U5") (pin "10") (pinfunction "PC2_10") (pintype "bidirectional"))
    )
    (net (code "188") (name "unconnected-(U5-PC3-Pad11)") (class "Default")
      (node (ref "U5") (pin "11") (pinfunction "PC3_11") (pintype "bidirectional"))
    )
    (net (code "189") (name "unconnected-(U5-PC5-Pad25)") (class "Default")
      (node (ref "U5") (pin "25") (pinfunction "PC5_25") (pintype "bidirectional"))
    )
    (net (code "190") (name "unconnected-(U5-PC9-Pad40)") (class "Default")
      (node (ref "U5") (pin "40") (pinfunction "PC9_40") (pintype "bidirectional"))
    )
    (net (code "191") (name "unconnected-(U6-DS-Pad10)") (class "Default")
      (node (ref "U6") (pin "10") (pinfunction "DS_10") (pintype "bidirectional"))
    )
    (net (code "192") (name "unconnected-(U6-~{Q7}-Pad7)") (class "Default")
      (node (ref "U6") (pin "7") (pinfunction "~{Q7}_7") (pintype "output"))
    )
    (net (code "193") (name "unconnected-(VR1-NC-Pad4)") (class "Default")
      (node (ref "VR1") (pin "4") (pinfunction "NC_4") (pintype "no_connect"))
    )
  )
)
